# DR.net
KiCad netlist of a schematic drawn in EAGLE
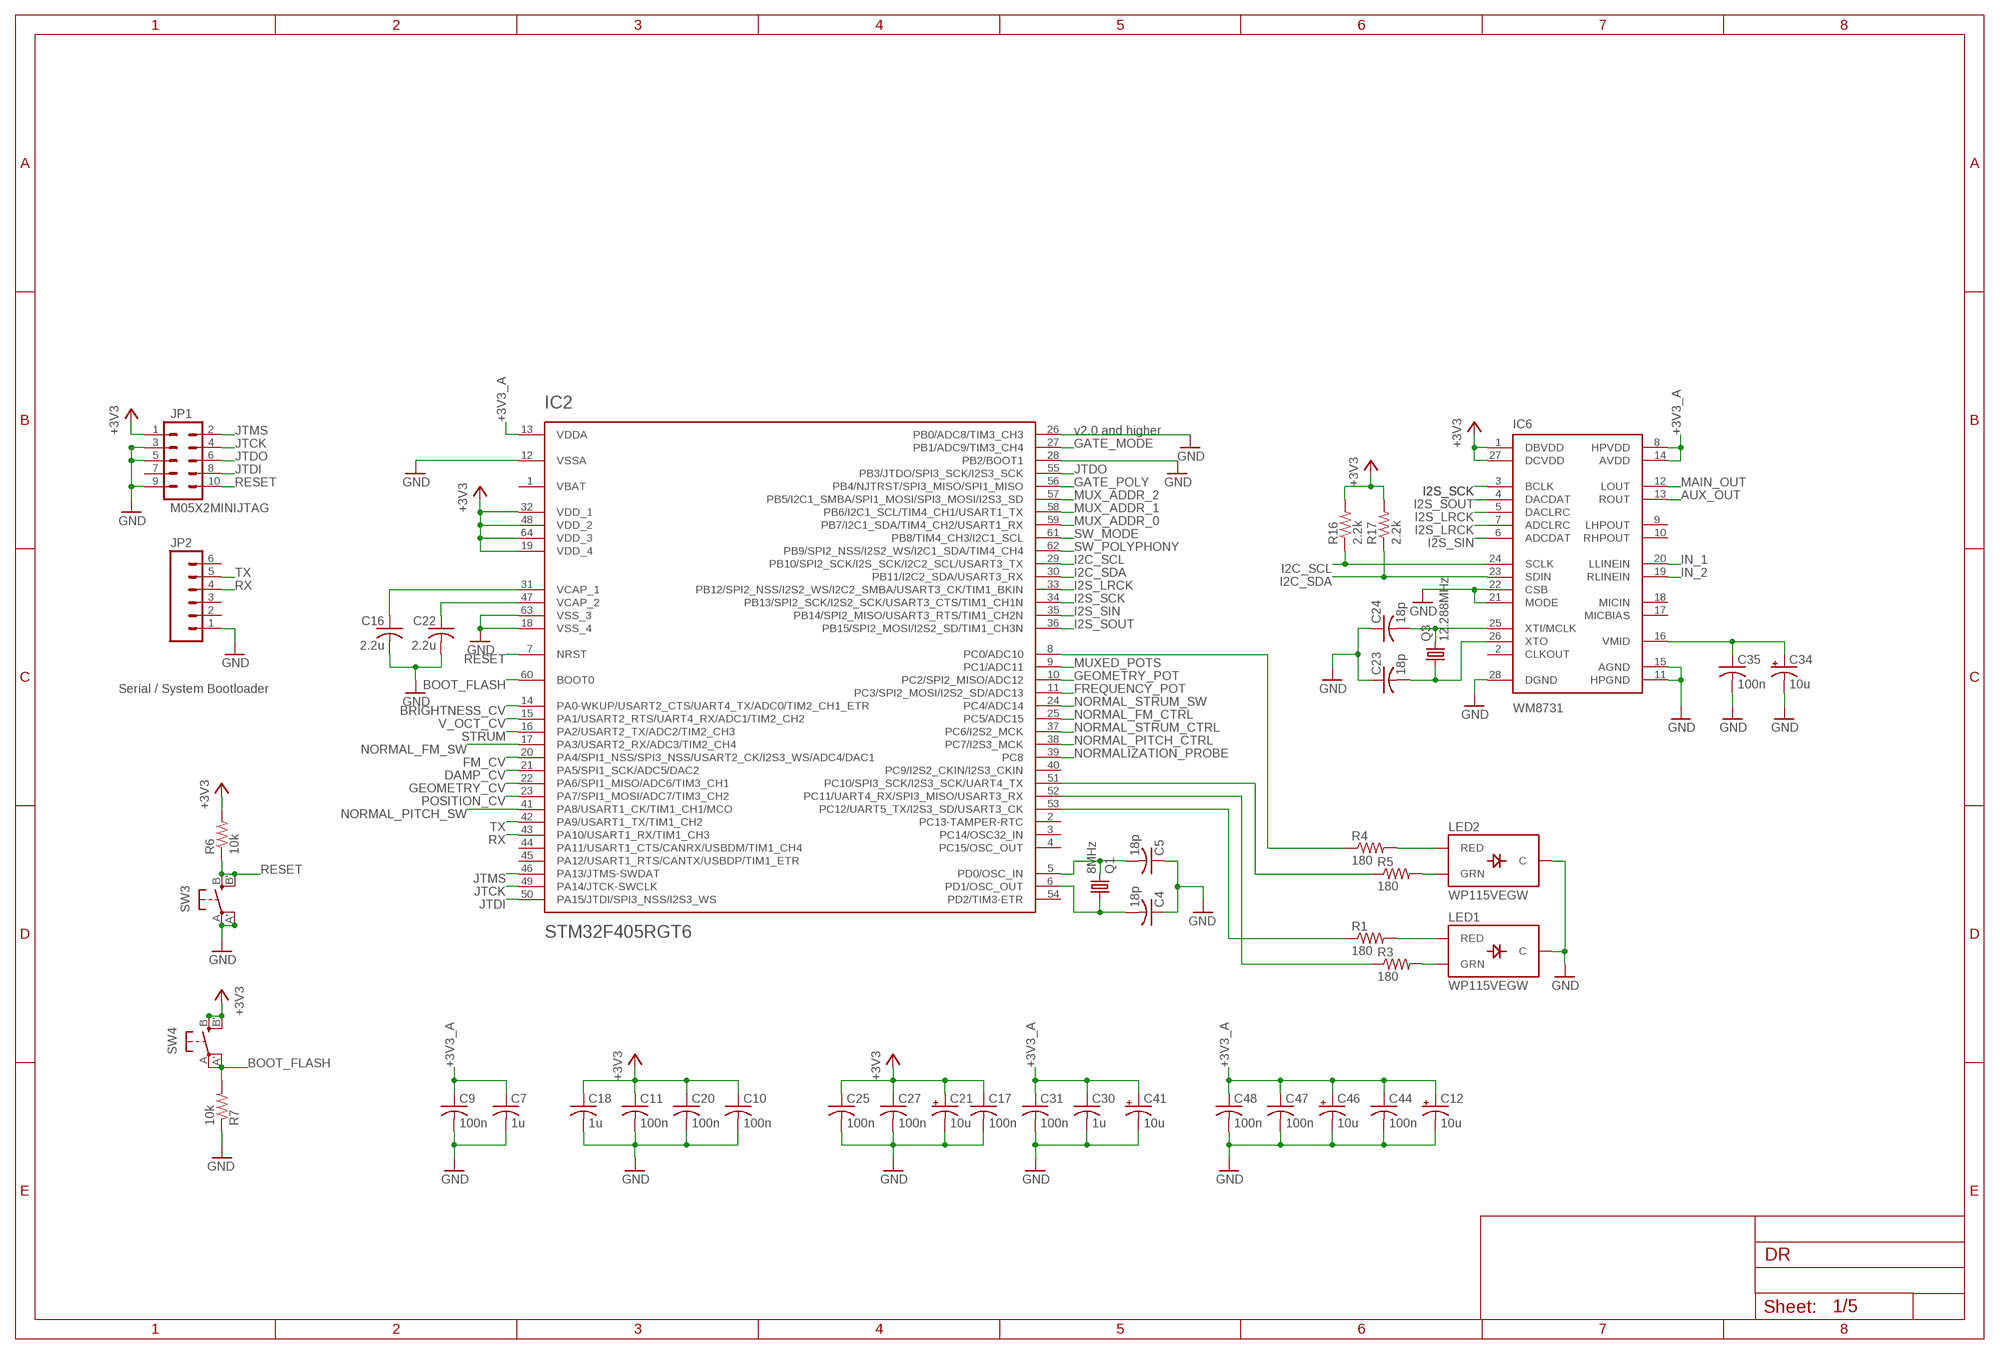
[diagram p0: schematic, sheet 1]
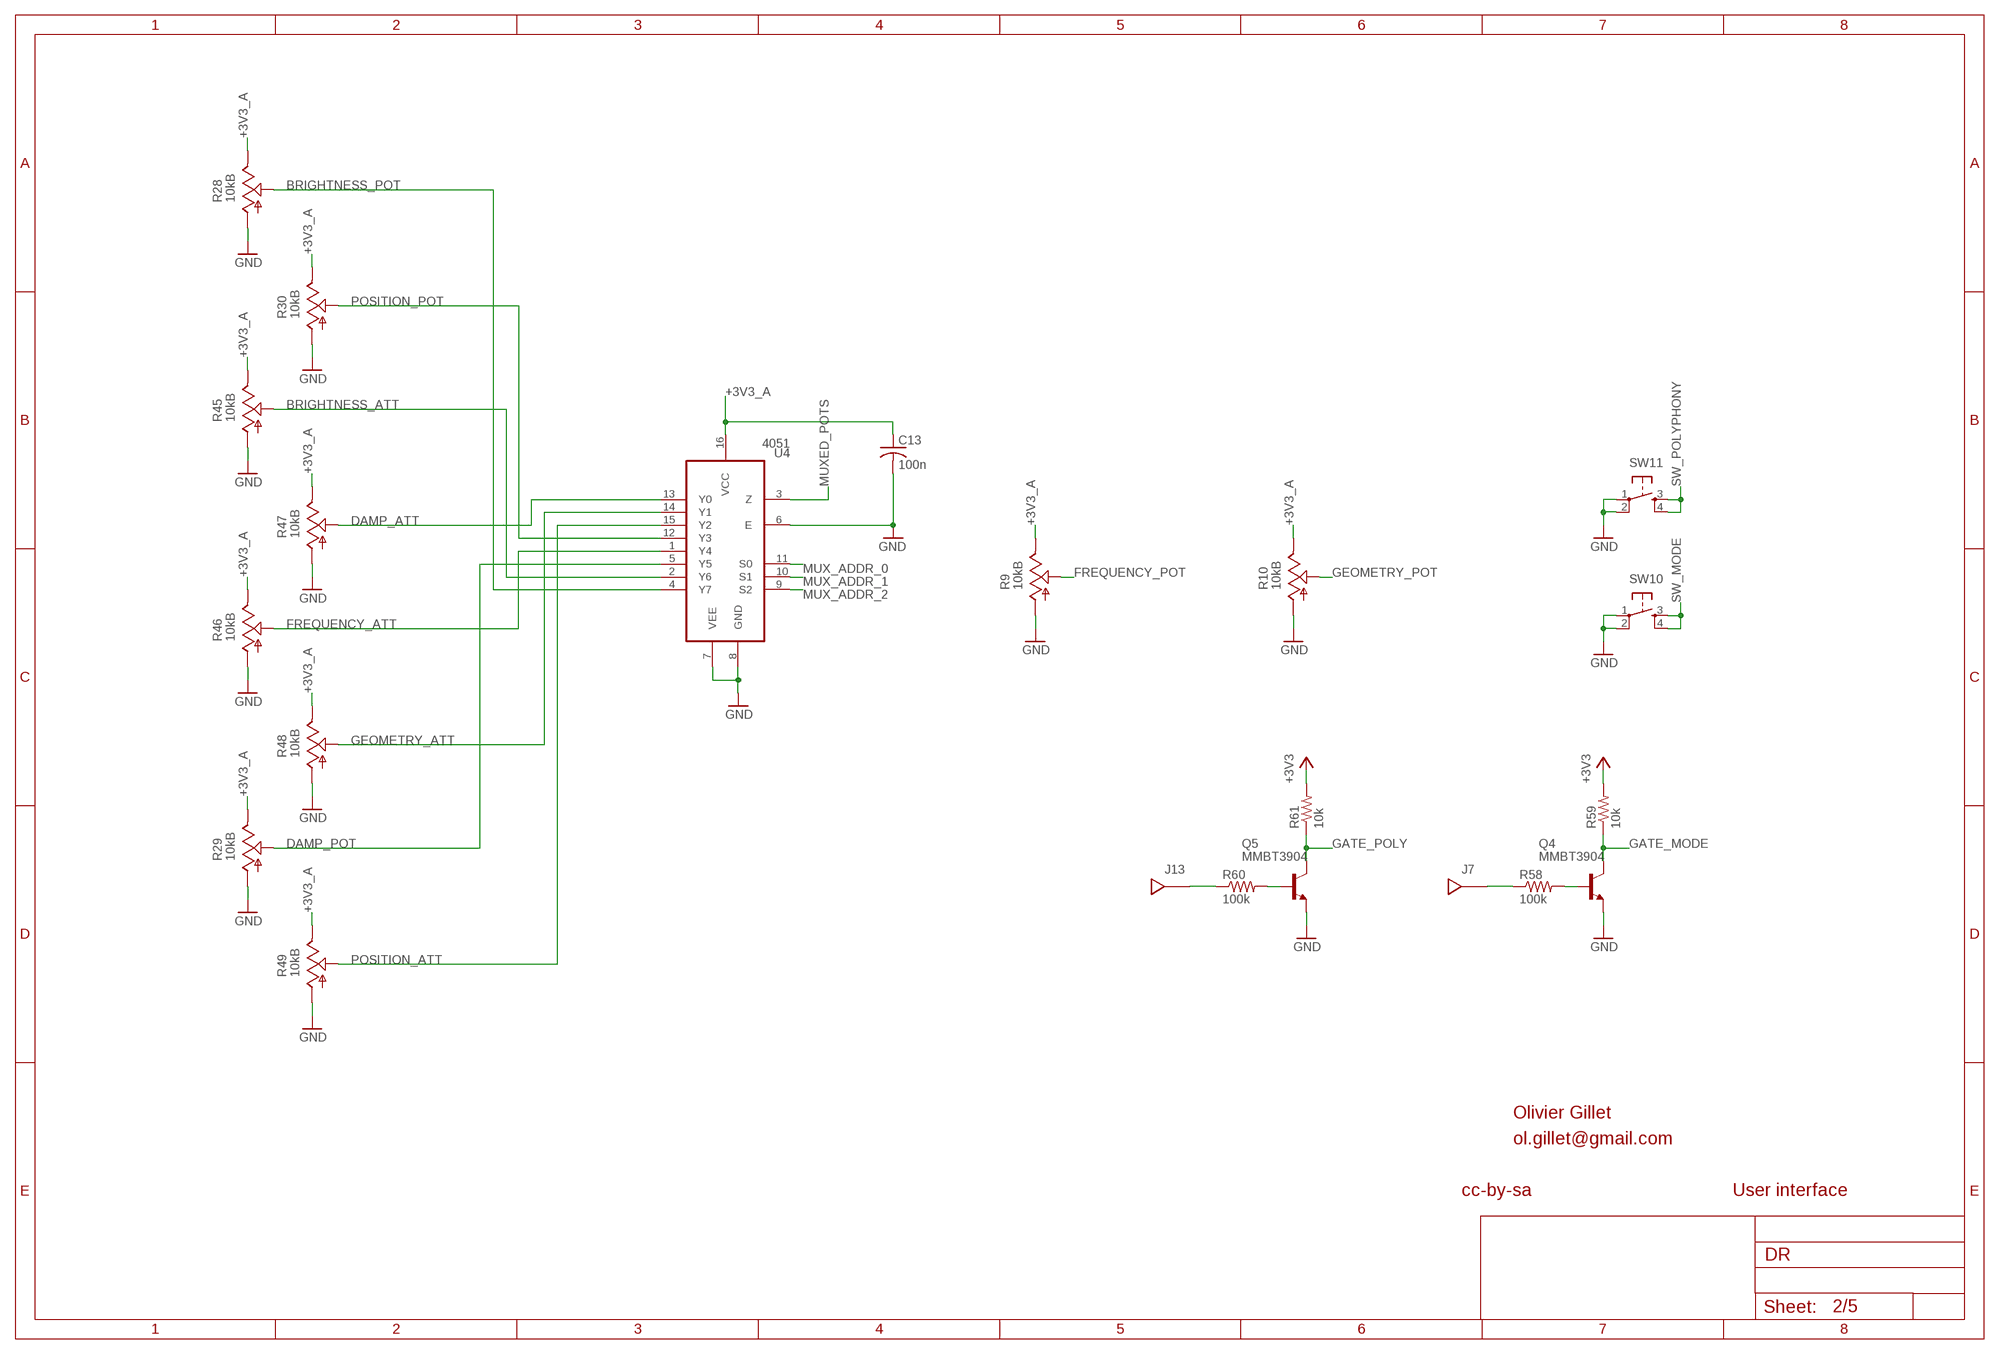
[diagram p1: schematic, sheet 2]
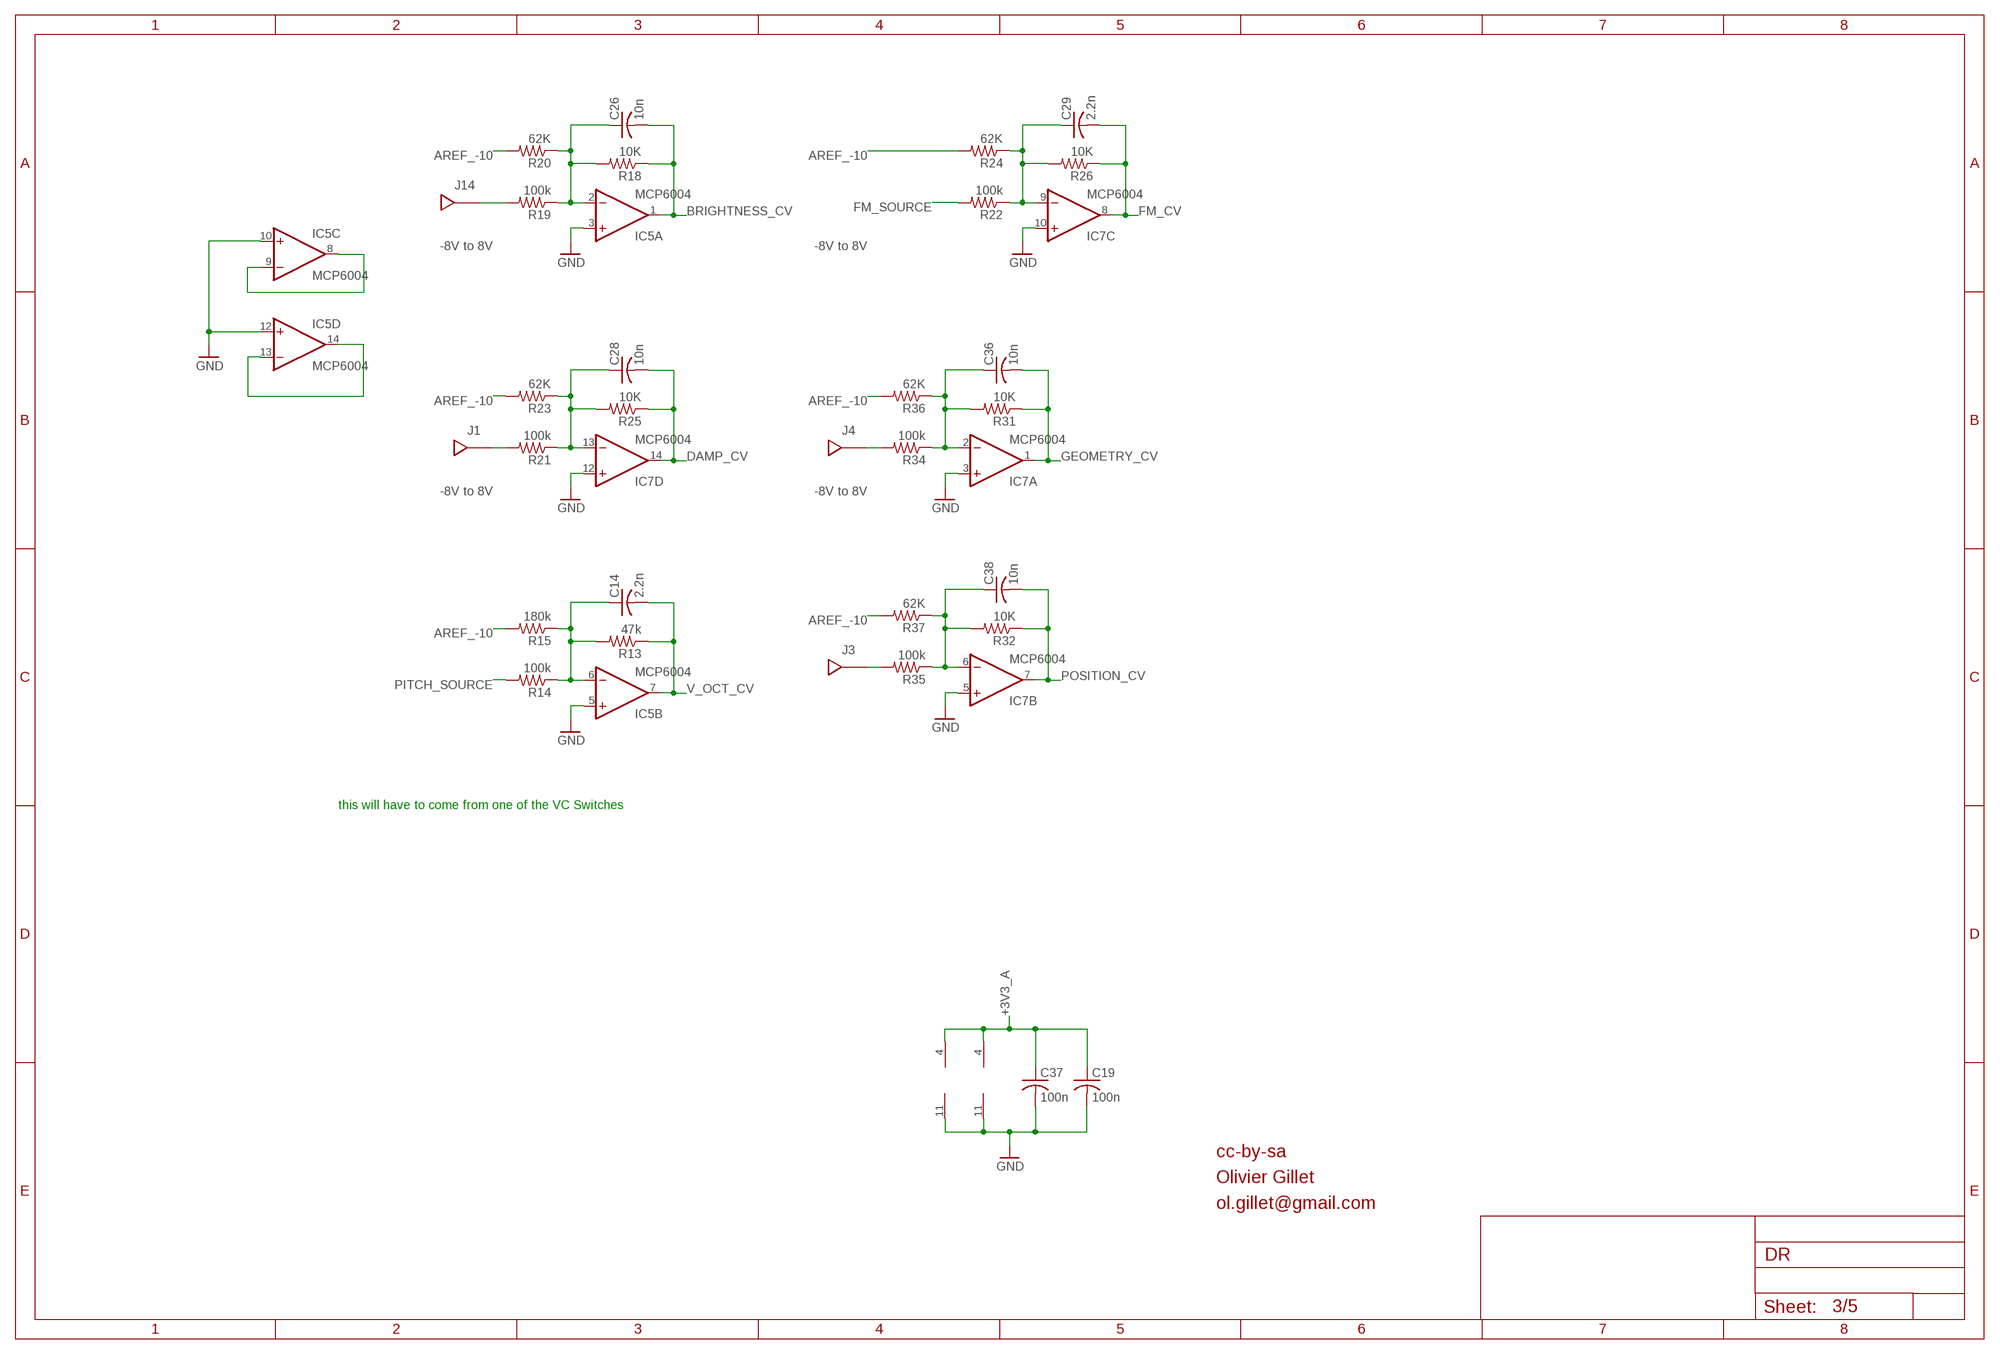
[diagram p2: schematic, sheet 3]
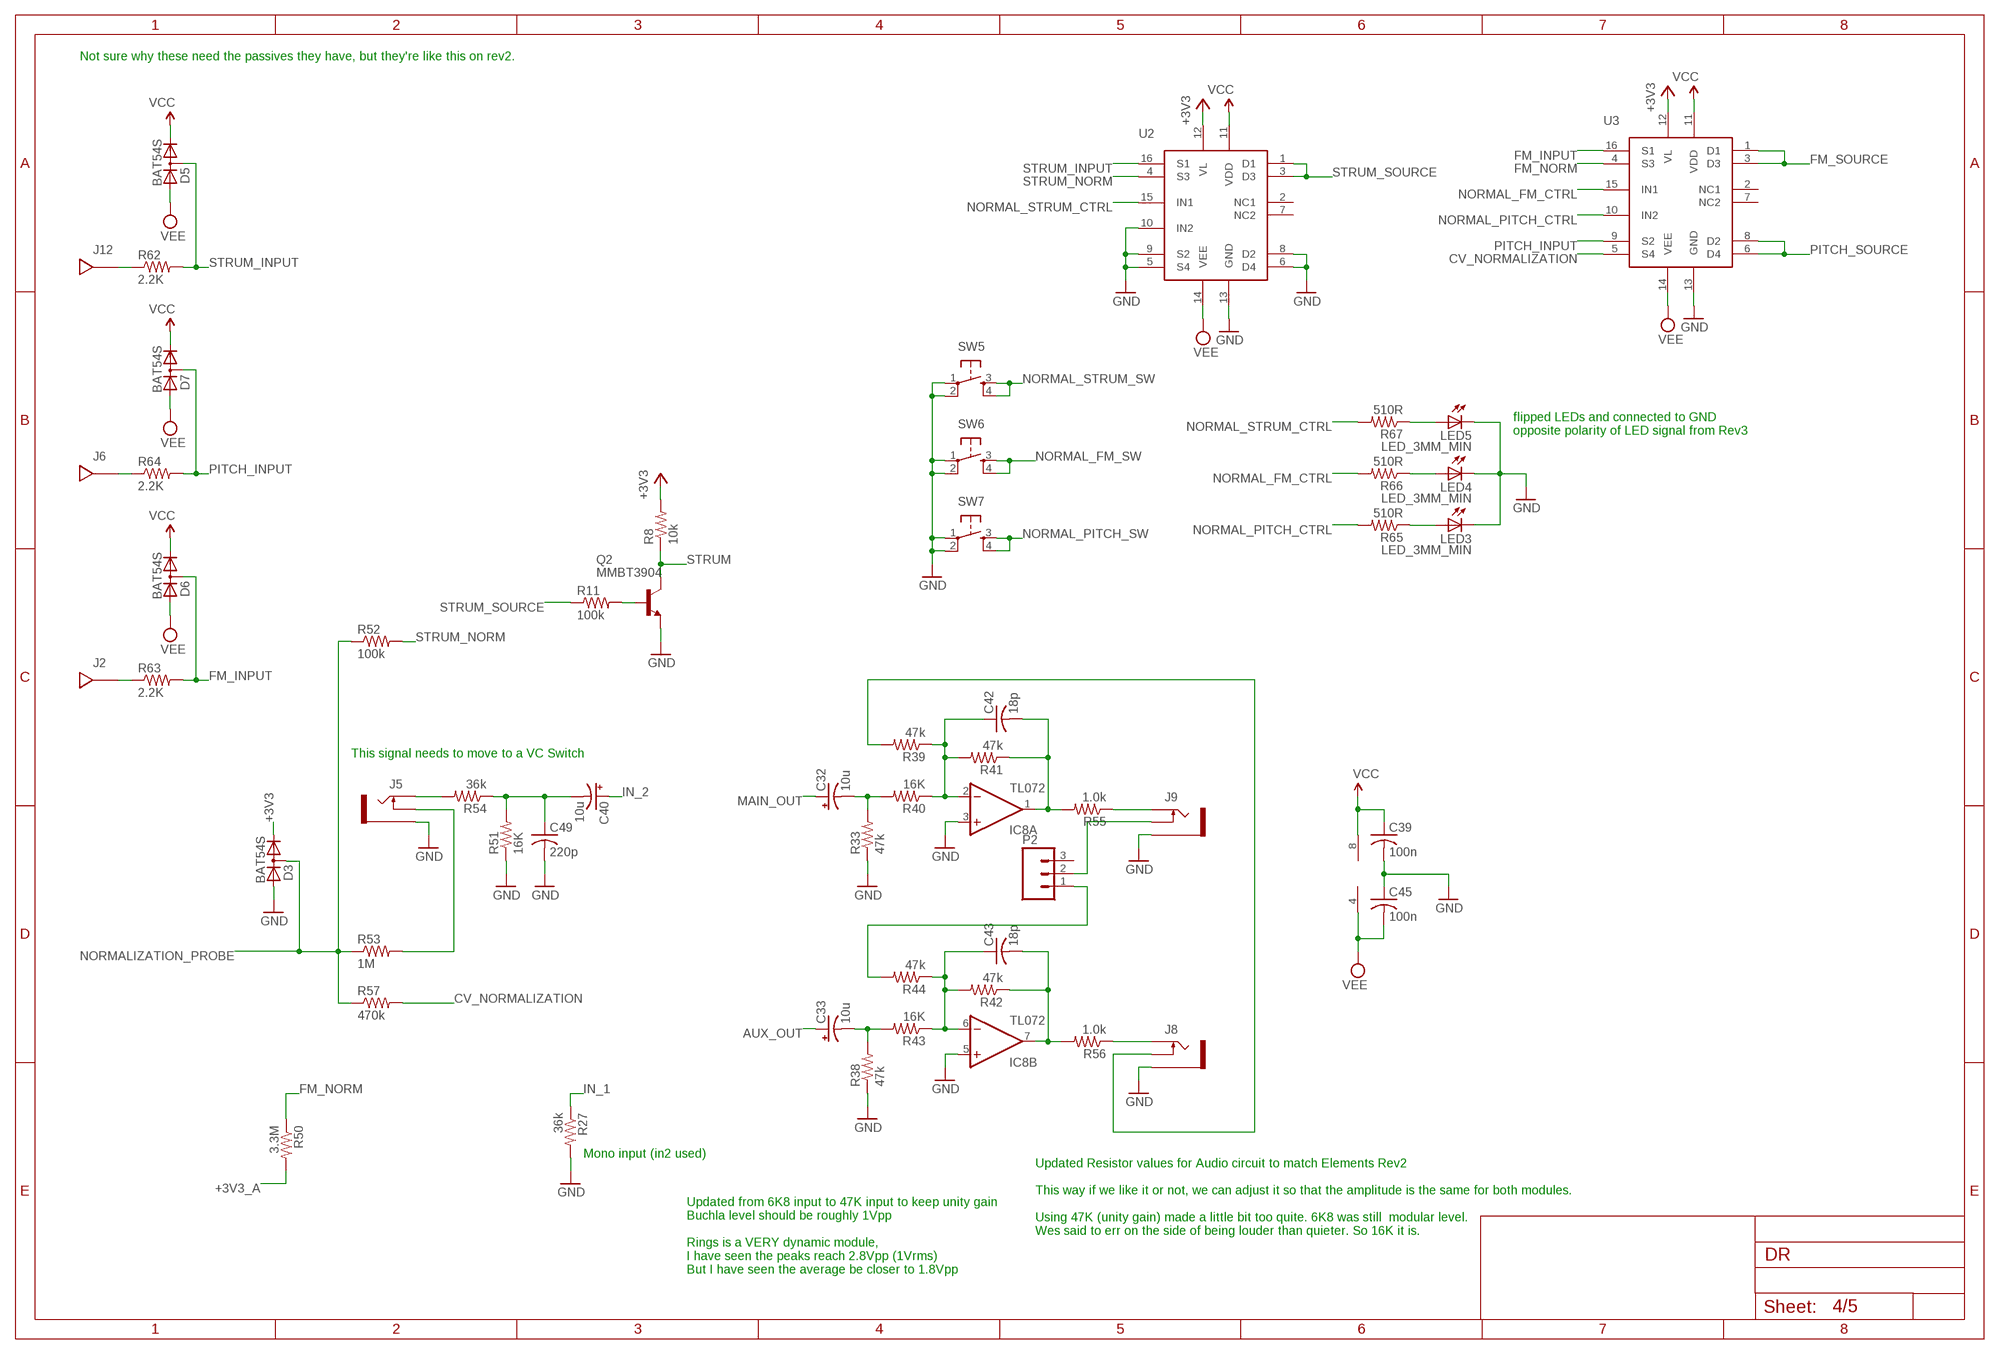
[diagram p3: schematic, sheet 4]
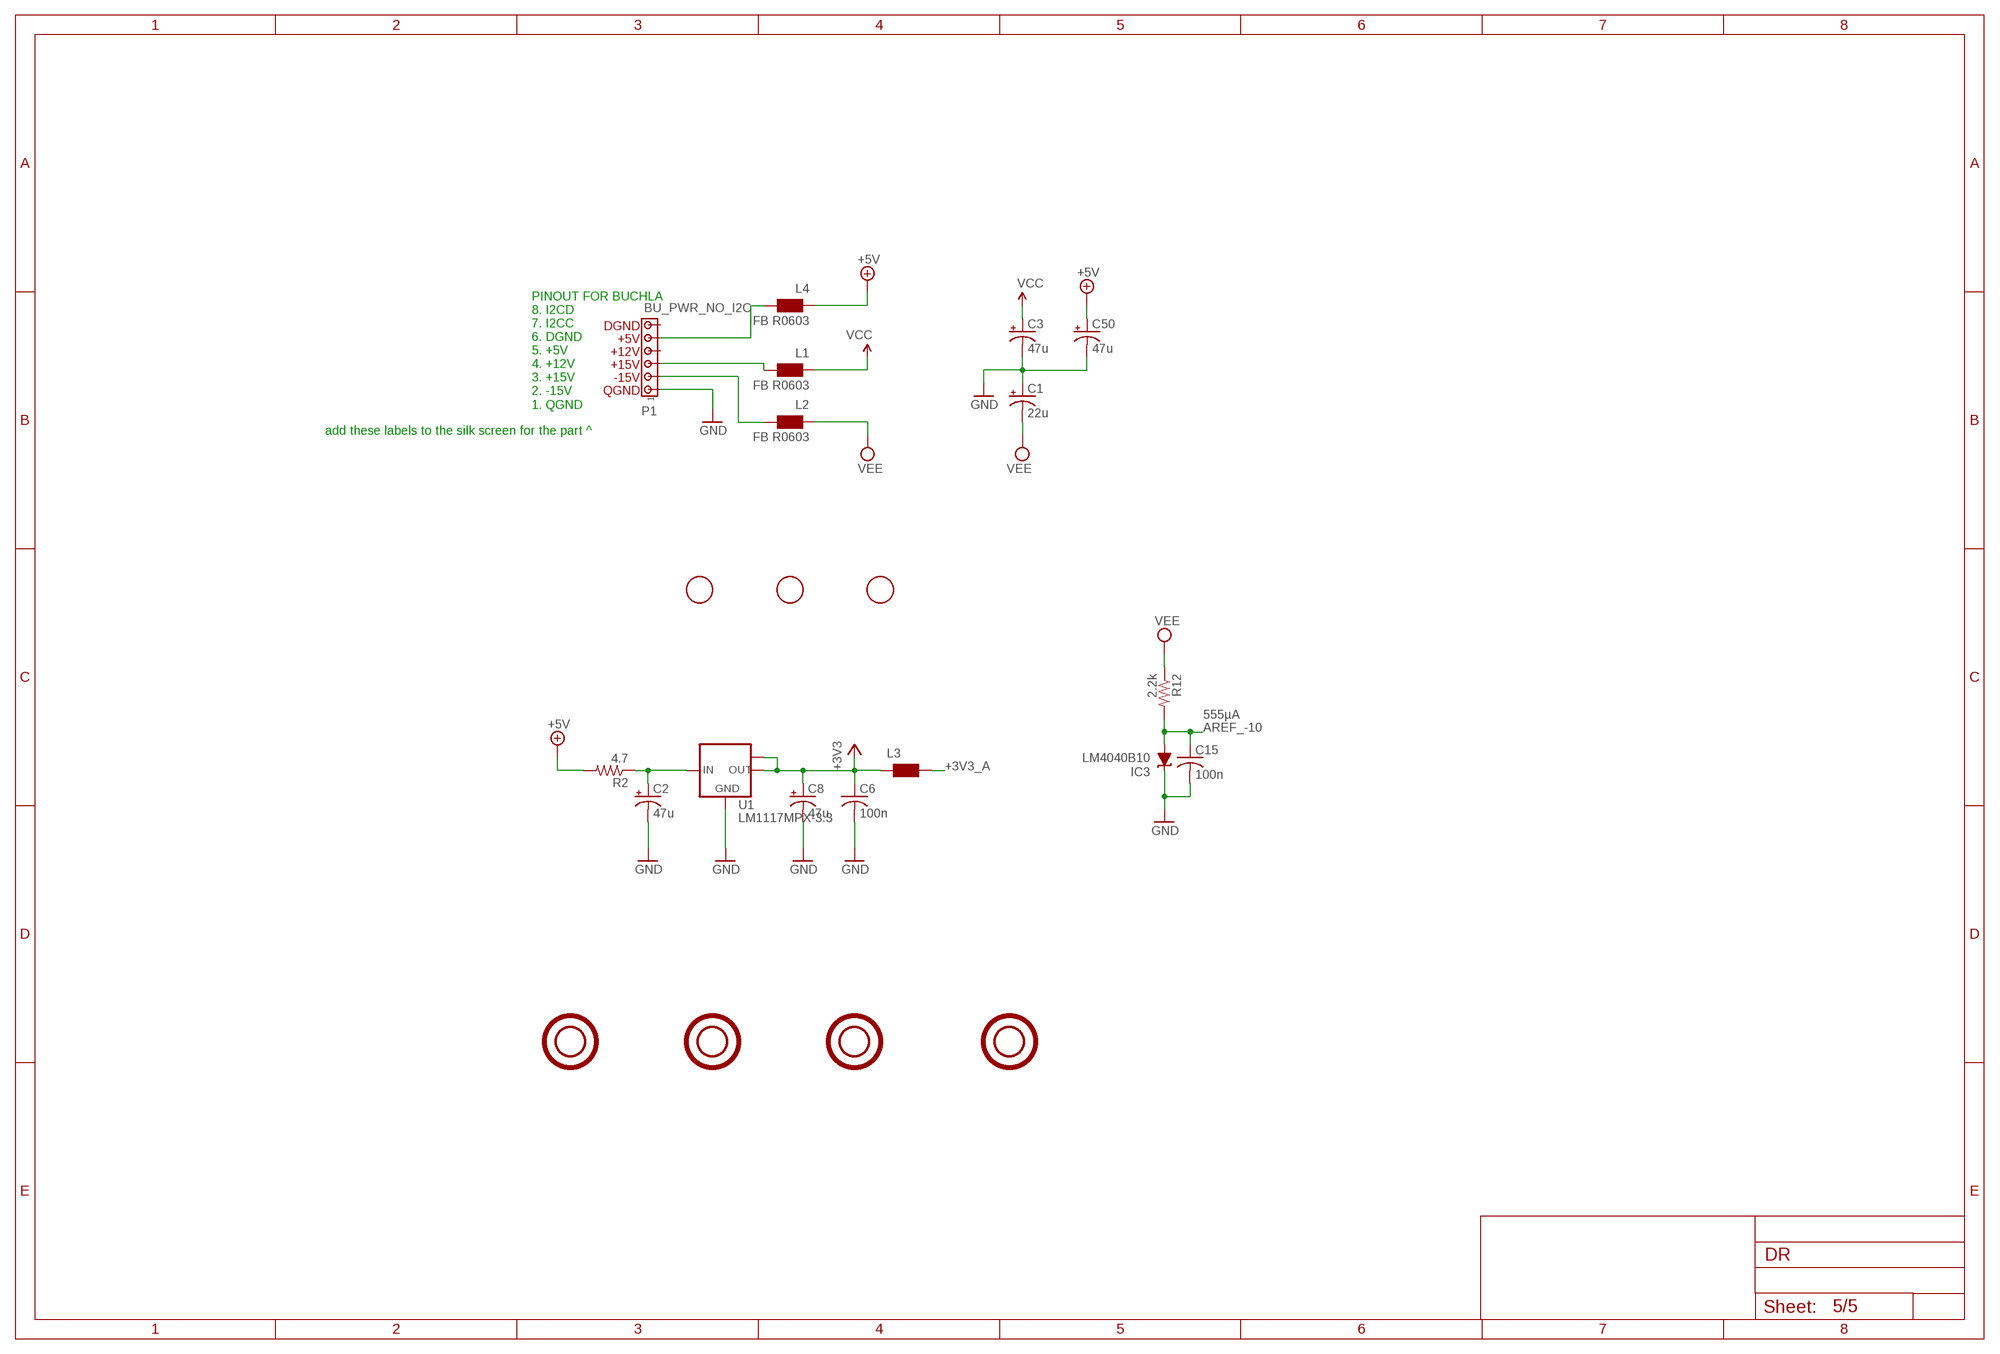
[diagram p4: schematic, sheet 5]

(export (version "E")
  (design (tool "Eeschema 10.0.6"))
  (components
    (comp (ref "C1")
      (value "22u")
      (footprint "eagle-import:PANASONIC_C")
      (libsource (lib "eagle-import") (part "CPOL-USC"))
    )
    (comp (ref "C2")
      (value "47u")
      (footprint "eagle-import:PANASONIC_D")
      (libsource (lib "eagle-import") (part "CPOL-USD"))
    )
    (comp (ref "C3")
      (value "47u")
      (footprint "eagle-import:PANASONIC_D")
      (libsource (lib "eagle-import") (part "CPOL-USD"))
    )
    (comp (ref "C6")
      (value "100n")
      (footprint "eagle-import:C0603")
      (libsource (lib "eagle-import") (part "C-USC0603"))
    )
    (comp (ref "C8")
      (value "47u")
      (footprint "eagle-import:PANASONIC_D")
      (libsource (lib "eagle-import") (part "CPOL-USD"))
    )
    (comp (ref "C15")
      (value "100n")
      (footprint "eagle-import:C0603")
      (libsource (lib "eagle-import") (part "C-USC0603"))
    )
    (comp (ref "C50")
      (value "47u")
      (footprint "eagle-import:PANASONIC_D")
      (libsource (lib "eagle-import") (part "CPOL-USD"))
    )
    (comp (ref "FD1")
      (value "FIDUCIAL")
      (footprint "eagle-import:FIDUCIAL_1MM")
      (libsource (lib "eagle-import") (part "FIDUCIAL"))
    )
    (comp (ref "FD2")
      (value "FIDUCIAL")
      (footprint "eagle-import:FIDUCIAL_1MM")
      (libsource (lib "eagle-import") (part "FIDUCIAL"))
    )
    (comp (ref "FD3")
      (value "FIDUCIAL")
      (footprint "eagle-import:FIDUCIAL_1MM")
      (libsource (lib "eagle-import") (part "FIDUCIAL"))
    )
    (comp (ref "H1")
      (value "3MM_MOUNT_HOLE")
      (footprint "eagle-import:3,0-PAD")
      (libsource (lib "eagle-import") (part "3MM_MOUNT_HOLE"))
    )
    (comp (ref "H2")
      (value "3MM_MOUNT_HOLE")
      (footprint "eagle-import:3,0-PAD")
      (libsource (lib "eagle-import") (part "3MM_MOUNT_HOLE"))
    )
    (comp (ref "H3")
      (value "3MM_MOUNT_HOLE")
      (footprint "eagle-import:3,0-PAD")
      (libsource (lib "eagle-import") (part "3MM_MOUNT_HOLE"))
    )
    (comp (ref "H4")
      (value "3MM_MOUNT_HOLE")
      (footprint "eagle-import:3,0-PAD")
      (libsource (lib "eagle-import") (part "3MM_MOUNT_HOLE"))
    )
    (comp (ref "IC3")
      (value "LM4040B10")
      (footprint "eagle-import:DBZ_R-PDSO-G3")
      (libsource (lib "eagle-import") (part "LM4041DBZB12"))
    )
    (comp (ref "L1")
      (value "FB R0603")
      (footprint "eagle-import:0603")
      (libsource (lib "eagle-import") (part "WE-CBF_0603"))
    )
    (comp (ref "L2")
      (value "FB R0603")
      (footprint "eagle-import:0603")
      (libsource (lib "eagle-import") (part "WE-CBF_0603"))
    )
    (comp (ref "L3")
      (value "WE-CBF_0603")
      (footprint "eagle-import:0603")
      (libsource (lib "eagle-import") (part "WE-CBF_0603"))
    )
    (comp (ref "L4")
      (value "FB R0603")
      (footprint "eagle-import:0603")
      (libsource (lib "eagle-import") (part "WE-CBF_0603"))
    )
    (comp (ref "P1")
      (value "BU_PWR_NO_I2C")
      (footprint "eagle-import:MTA_156")
      (libsource (lib "eagle-import") (part "BU_PWR_NO_I2C"))
    )
    (comp (ref "R2")
      (value "4.7")
      (footprint "eagle-import:R1206")
      (libsource (lib "eagle-import") (part "R-US_R1206"))
    )
    (comp (ref "R12")
      (value "2.2k")
      (footprint "eagle-import:R0603")
      (libsource (lib "eagle-import") (part "R-US_R0603"))
    )
    (comp (ref "U1")
      (value "LM1117MPX-3.3")
      (footprint "eagle-import:SOT223")
      (libsource (lib "eagle-import") (part "LM1117MPX-3.3"))
    )
    (comp (ref "C4")
      (value "18p")
      (footprint "eagle-import:C0603")
      (libsource (lib "eagle-import") (part "C-USC0603"))
    )
    (comp (ref "C5")
      (value "18p")
      (footprint "eagle-import:C0603")
      (libsource (lib "eagle-import") (part "C-USC0603"))
    )
    (comp (ref "C7")
      (value "1u")
      (footprint "eagle-import:C0603")
      (libsource (lib "eagle-import") (part "C-USC0603"))
    )
    (comp (ref "C9")
      (value "100n")
      (footprint "eagle-import:C0603")
      (libsource (lib "eagle-import") (part "C-USC0603"))
    )
    (comp (ref "C10")
      (value "100n")
      (footprint "eagle-import:C0603")
      (libsource (lib "eagle-import") (part "C-USC0603"))
    )
    (comp (ref "C11")
      (value "100n")
      (footprint "eagle-import:C0603")
      (libsource (lib "eagle-import") (part "C-USC0603"))
    )
    (comp (ref "C12")
      (value "10u")
      (footprint "eagle-import:PANASONIC_A")
      (libsource (lib "eagle-import") (part "CPOL-USA"))
    )
    (comp (ref "C16")
      (value "2.2u")
      (footprint "eagle-import:C0805")
      (libsource (lib "eagle-import") (part "C-USC0805"))
    )
    (comp (ref "C17")
      (value "100n")
      (footprint "eagle-import:C0603")
      (libsource (lib "eagle-import") (part "C-USC0603"))
    )
    (comp (ref "C18")
      (value "1u")
      (footprint "eagle-import:C0603")
      (libsource (lib "eagle-import") (part "C-USC0603"))
    )
    (comp (ref "C20")
      (value "100n")
      (footprint "eagle-import:C0603")
      (libsource (lib "eagle-import") (part "C-USC0603"))
    )
    (comp (ref "C21")
      (value "10u")
      (footprint "eagle-import:PANASONIC_A")
      (libsource (lib "eagle-import") (part "CPOL-USA"))
    )
    (comp (ref "C22")
      (value "2.2u")
      (footprint "eagle-import:C0805")
      (libsource (lib "eagle-import") (part "C-USC0805"))
    )
    (comp (ref "C23")
      (value "18p")
      (footprint "eagle-import:C0603")
      (libsource (lib "eagle-import") (part "C-USC0603"))
    )
    (comp (ref "C24")
      (value "18p")
      (footprint "eagle-import:C0603")
      (libsource (lib "eagle-import") (part "C-USC0603"))
    )
    (comp (ref "C25")
      (value "100n")
      (footprint "eagle-import:C0603")
      (libsource (lib "eagle-import") (part "C-USC0603"))
    )
    (comp (ref "C27")
      (value "100n")
      (footprint "eagle-import:C0603")
      (libsource (lib "eagle-import") (part "C-USC0603"))
    )
    (comp (ref "C30")
      (value "1u")
      (footprint "eagle-import:C0603")
      (libsource (lib "eagle-import") (part "C-USC0603"))
    )
    (comp (ref "C31")
      (value "100n")
      (footprint "eagle-import:C0603")
      (libsource (lib "eagle-import") (part "C-USC0603"))
    )
    (comp (ref "C34")
      (value "10u")
      (footprint "eagle-import:PANASONIC_A")
      (libsource (lib "eagle-import") (part "CPOL-USA"))
    )
    (comp (ref "C35")
      (value "100n")
      (footprint "eagle-import:C0603")
      (libsource (lib "eagle-import") (part "C-USC0603"))
    )
    (comp (ref "C41")
      (value "10u")
      (footprint "eagle-import:PANASONIC_A")
      (libsource (lib "eagle-import") (part "CPOL-USA"))
    )
    (comp (ref "C44")
      (value "100n")
      (footprint "eagle-import:C0603")
      (libsource (lib "eagle-import") (part "C-USC0603"))
    )
    (comp (ref "C46")
      (value "10u")
      (footprint "eagle-import:PANASONIC_A")
      (libsource (lib "eagle-import") (part "CPOL-USA"))
    )
    (comp (ref "C47")
      (value "100n")
      (footprint "eagle-import:C0603")
      (libsource (lib "eagle-import") (part "C-USC0603"))
    )
    (comp (ref "C48")
      (value "100n")
      (footprint "eagle-import:C0603")
      (libsource (lib "eagle-import") (part "C-USC0603"))
    )
    (comp (ref "IC2")
      (value "STM32F405RGT6")
      (footprint "eagle-import:TQFP-10X10-64")
      (libsource (lib "eagle-import") (part "STM32F20X"))
    )
    (comp (ref "IC6")
      (value "WM8731")
      (footprint "eagle-import:SSOP28")
      (libsource (lib "eagle-import") (part "WM8731"))
    )
    (comp (ref "JP1")
      (value "M05X2MINIJTAG")
      (footprint "eagle-import:2X5-1.27")
      (libsource (lib "eagle-import") (part "M05X2MINIJTAG"))
    )
    (comp (ref "JP2")
      (value "M06SIP")
      (footprint "eagle-import:1X06")
      (libsource (lib "eagle-import") (part "M06SIP"))
    )
    (comp (ref "LED1")
      (value "WP115VEGW")
      (footprint "eagle-import:LED-BICOLOR-THROUGHHOLE")
      (libsource (lib "eagle-import") (part "LED-BICOLOR-THROUGHHOLE"))
    )
    (comp (ref "LED2")
      (value "WP115VEGW")
      (footprint "eagle-import:LED-BICOLOR-THROUGHHOLE")
      (libsource (lib "eagle-import") (part "LED-BICOLOR-THROUGHHOLE"))
    )
    (comp (ref "Q1")
      (value "8MHz")
      (footprint "eagle-import:HC49UP")
      (libsource (lib "eagle-import") (part "CRYSTALHC49UP"))
    )
    (comp (ref "Q3")
      (value "12.288MHz")
      (footprint "eagle-import:HC49UP")
      (libsource (lib "eagle-import") (part "CRYSTALHC49UP"))
    )
    (comp (ref "R1")
      (value "180")
      (footprint "eagle-import:R0603")
      (libsource (lib "eagle-import") (part "R-US_R0603"))
    )
    (comp (ref "R3")
      (value "180")
      (footprint "eagle-import:R0603")
      (libsource (lib "eagle-import") (part "R-US_R0603"))
    )
    (comp (ref "R4")
      (value "180")
      (footprint "eagle-import:R0603")
      (libsource (lib "eagle-import") (part "R-US_R0603"))
    )
    (comp (ref "R5")
      (value "180")
      (footprint "eagle-import:R0603")
      (libsource (lib "eagle-import") (part "R-US_R0603"))
    )
    (comp (ref "R6")
      (value "10k")
      (footprint "eagle-import:R0603")
      (libsource (lib "eagle-import") (part "R-US_R0603"))
    )
    (comp (ref "R7")
      (value "10k")
      (footprint "eagle-import:R0603")
      (libsource (lib "eagle-import") (part "R-US_R0603"))
    )
    (comp (ref "R16")
      (value "2.2k")
      (footprint "eagle-import:R0603")
      (libsource (lib "eagle-import") (part "R-US_R0603"))
    )
    (comp (ref "R17")
      (value "2.2k")
      (footprint "eagle-import:R0603")
      (libsource (lib "eagle-import") (part "R-US_R0603"))
    )
    (comp (ref "SW3")
      (value "EVQQ2")
      (footprint "eagle-import:EVQ-Q2")
      (libsource (lib "eagle-import") (part "EVQQ2"))
    )
    (comp (ref "SW4")
      (value "EVQQ2")
      (footprint "eagle-import:EVQ-Q2")
      (libsource (lib "eagle-import") (part "EVQQ2"))
    )
    (comp (ref "C14")
      (value "2.2n")
      (footprint "eagle-import:C0603")
      (libsource (lib "eagle-import") (part "C-USC0603"))
    )
    (comp (ref "C19")
      (value "100n")
      (footprint "eagle-import:C0603")
      (libsource (lib "eagle-import") (part "C-USC0603"))
    )
    (comp (ref "C26")
      (value "10n")
      (footprint "eagle-import:C0603")
      (libsource (lib "eagle-import") (part "C-USC0603"))
    )
    (comp (ref "C28")
      (value "10n")
      (footprint "eagle-import:C0603")
      (libsource (lib "eagle-import") (part "C-USC0603"))
    )
    (comp (ref "C29")
      (value "2.2n")
      (footprint "eagle-import:C0603")
      (libsource (lib "eagle-import") (part "C-USC0603"))
    )
    (comp (ref "C36")
      (value "10n")
      (footprint "eagle-import:C0603")
      (libsource (lib "eagle-import") (part "C-USC0603"))
    )
    (comp (ref "C37")
      (value "100n")
      (footprint "eagle-import:C0603")
      (libsource (lib "eagle-import") (part "C-USC0603"))
    )
    (comp (ref "C38")
      (value "10n")
      (footprint "eagle-import:C0603")
      (libsource (lib "eagle-import") (part "C-USC0603"))
    )
    (comp (ref "IC5")
      (value "MCP6004")
      (footprint "eagle-import:SO14")
      (libsource (lib "eagle-import") (part "QUAD_OPAMPD"))
    )
    (comp (ref "IC7")
      (value "MCP6004")
      (footprint "eagle-import:SO14")
      (libsource (lib "eagle-import") (part "QUAD_OPAMPD"))
    )
    (comp (ref "J1")
      (value "JOHNSON_BANANASTD")
      (footprint "eagle-import:JOHNSON")
      (libsource (lib "eagle-import") (part "JOHNSON_BANANASTD"))
    )
    (comp (ref "J3")
      (value "JOHNSON_BANANASTD")
      (footprint "eagle-import:JOHNSON")
      (libsource (lib "eagle-import") (part "JOHNSON_BANANASTD"))
    )
    (comp (ref "J4")
      (value "JOHNSON_BANANASTD")
      (footprint "eagle-import:JOHNSON")
      (libsource (lib "eagle-import") (part "JOHNSON_BANANASTD"))
    )
    (comp (ref "J14")
      (value "JOHNSON_BANANASTD")
      (footprint "eagle-import:JOHNSON")
      (libsource (lib "eagle-import") (part "JOHNSON_BANANASTD"))
    )
    (comp (ref "R13")
      (value "47k")
      (footprint "eagle-import:R0603")
      (libsource (lib "eagle-import") (part "R-US_R0603"))
    )
    (comp (ref "R14")
      (value "100k")
      (footprint "eagle-import:R0603")
      (libsource (lib "eagle-import") (part "R-US_R0603"))
    )
    (comp (ref "R15")
      (value "180k")
      (footprint "eagle-import:R0603")
      (libsource (lib "eagle-import") (part "R-US_R0603"))
    )
    (comp (ref "R18")
      (value "10K")
      (footprint "eagle-import:R0603")
      (libsource (lib "eagle-import") (part "R-US_R0603"))
    )
    (comp (ref "R19")
      (value "100k")
      (footprint "eagle-import:R0603")
      (libsource (lib "eagle-import") (part "R-US_R0603"))
    )
    (comp (ref "R20")
      (value "62K")
      (footprint "eagle-import:R0603")
      (libsource (lib "eagle-import") (part "R-US_R0603"))
    )
    (comp (ref "R21")
      (value "100k")
      (footprint "eagle-import:R0603")
      (libsource (lib "eagle-import") (part "R-US_R0603"))
    )
    (comp (ref "R22")
      (value "100k")
      (footprint "eagle-import:R0603")
      (libsource (lib "eagle-import") (part "R-US_R0603"))
    )
    (comp (ref "R23")
      (value "62K")
      (footprint "eagle-import:R0603")
      (libsource (lib "eagle-import") (part "R-US_R0603"))
    )
    (comp (ref "R24")
      (value "62K")
      (footprint "eagle-import:R0603")
      (libsource (lib "eagle-import") (part "R-US_R0603"))
    )
    (comp (ref "R25")
      (value "10K")
      (footprint "eagle-import:R0603")
      (libsource (lib "eagle-import") (part "R-US_R0603"))
    )
    (comp (ref "R26")
      (value "10K")
      (footprint "eagle-import:R0603")
      (libsource (lib "eagle-import") (part "R-US_R0603"))
    )
    (comp (ref "R31")
      (value "10K")
      (footprint "eagle-import:R0603")
      (libsource (lib "eagle-import") (part "R-US_R0603"))
    )
    (comp (ref "R32")
      (value "10K")
      (footprint "eagle-import:R0603")
      (libsource (lib "eagle-import") (part "R-US_R0603"))
    )
    (comp (ref "R34")
      (value "100k")
      (footprint "eagle-import:R0603")
      (libsource (lib "eagle-import") (part "R-US_R0603"))
    )
    (comp (ref "R35")
      (value "100k")
      (footprint "eagle-import:R0603")
      (libsource (lib "eagle-import") (part "R-US_R0603"))
    )
    (comp (ref "R36")
      (value "62K")
      (footprint "eagle-import:R0603")
      (libsource (lib "eagle-import") (part "R-US_R0603"))
    )
    (comp (ref "R37")
      (value "62K")
      (footprint "eagle-import:R0603")
      (libsource (lib "eagle-import") (part "R-US_R0603"))
    )
    (comp (ref "C13")
      (value "100n")
      (footprint "eagle-import:C0603")
      (libsource (lib "eagle-import") (part "C-USC0603"))
    )
    (comp (ref "J7")
      (value "JOHNSON_BANANASTD")
      (footprint "eagle-import:JOHNSON")
      (libsource (lib "eagle-import") (part "JOHNSON_BANANASTD"))
    )
    (comp (ref "J13")
      (value "JOHNSON_BANANASTD")
      (footprint "eagle-import:JOHNSON")
      (libsource (lib "eagle-import") (part "JOHNSON_BANANASTD"))
    )
    (comp (ref "Q4")
      (value "MMBT3904")
      (footprint "eagle-import:SOT23-BEC")
      (libsource (lib "eagle-import") (part "-NPN-SOT23-BECMMBT3904LT1"))
    )
    (comp (ref "Q5")
      (value "MMBT3904")
      (footprint "eagle-import:SOT23-BEC")
      (libsource (lib "eagle-import") (part "-NPN-SOT23-BECMMBT3904LT1"))
    )
    (comp (ref "R9")
      (value "10kB")
      (footprint "eagle-import:ALPS_POT_VERTICAL_PS")
      (libsource (lib "eagle-import") (part "POT_USVERTICAL_PS"))
    )
    (comp (ref "R10")
      (value "10kB")
      (footprint "eagle-import:ALPS_POT_VERTICAL_PS")
      (libsource (lib "eagle-import") (part "POT_USVERTICAL_PS"))
    )
    (comp (ref "R28")
      (value "10kB")
      (footprint "eagle-import:ALPS_POT_VERTICAL_PS")
      (libsource (lib "eagle-import") (part "POT_USVERTICAL_PS"))
    )
    (comp (ref "R29")
      (value "10kB")
      (footprint "eagle-import:ALPS_POT_VERTICAL_PS")
      (libsource (lib "eagle-import") (part "POT_USVERTICAL_PS"))
    )
    (comp (ref "R30")
      (value "10kB")
      (footprint "eagle-import:ALPS_POT_VERTICAL_PS")
      (libsource (lib "eagle-import") (part "POT_USVERTICAL_PS"))
    )
    (comp (ref "R45")
      (value "10kB")
      (footprint "eagle-import:ALPS_POT_VERTICAL")
      (libsource (lib "eagle-import") (part "POT_USVERTICAL"))
    )
    (comp (ref "R46")
      (value "10kB")
      (footprint "eagle-import:ALPS_POT_VERTICAL")
      (libsource (lib "eagle-import") (part "POT_USVERTICAL"))
    )
    (comp (ref "R47")
      (value "10kB")
      (footprint "eagle-import:ALPS_POT_VERTICAL")
      (libsource (lib "eagle-import") (part "POT_USVERTICAL"))
    )
    (comp (ref "R48")
      (value "10kB")
      (footprint "eagle-import:ALPS_POT_VERTICAL")
      (libsource (lib "eagle-import") (part "POT_USVERTICAL"))
    )
    (comp (ref "R49")
      (value "10kB")
      (footprint "eagle-import:ALPS_POT_VERTICAL")
      (libsource (lib "eagle-import") (part "POT_USVERTICAL"))
    )
    (comp (ref "R58")
      (value "100k")
      (footprint "eagle-import:R0603")
      (libsource (lib "eagle-import") (part "R-US_R0603"))
    )
    (comp (ref "R59")
      (value "10k")
      (footprint "eagle-import:R0603")
      (libsource (lib "eagle-import") (part "R-US_R0603"))
    )
    (comp (ref "R60")
      (value "100k")
      (footprint "eagle-import:R0603")
      (libsource (lib "eagle-import") (part "R-US_R0603"))
    )
    (comp (ref "R61")
      (value "10k")
      (footprint "eagle-import:R0603")
      (libsource (lib "eagle-import") (part "R-US_R0603"))
    )
    (comp (ref "SW10")
      (value "TAC_SWITCH")
      (footprint "eagle-import:C&K_D6R")
      (libsource (lib "eagle-import") (part "TAC_SWITCH"))
    )
    (comp (ref "SW11")
      (value "TAC_SWITCH")
      (footprint "eagle-import:C&K_D6R")
      (libsource (lib "eagle-import") (part "TAC_SWITCH"))
    )
    (comp (ref "U4")
      (value "4051")
      (footprint "eagle-import:SO16")
      (libsource (lib "eagle-import") (part "4051"))
    )
    (comp (ref "C32")
      (value "10u")
      (footprint "eagle-import:PANASONIC_A")
      (libsource (lib "eagle-import") (part "CPOL-USA"))
    )
    (comp (ref "C33")
      (value "10u")
      (footprint "eagle-import:PANASONIC_A")
      (libsource (lib "eagle-import") (part "CPOL-USA"))
    )
    (comp (ref "C39")
      (value "100n")
      (footprint "eagle-import:C0603")
      (libsource (lib "eagle-import") (part "C-USC0603"))
    )
    (comp (ref "C40")
      (value "10u")
      (footprint "eagle-import:PANASONIC_A")
      (libsource (lib "eagle-import") (part "CPOL-USA"))
    )
    (comp (ref "C42")
      (value "18p")
      (footprint "eagle-import:C0603")
      (libsource (lib "eagle-import") (part "C-USC0603"))
    )
    (comp (ref "C43")
      (value "18p")
      (footprint "eagle-import:C0603")
      (libsource (lib "eagle-import") (part "C-USC0603"))
    )
    (comp (ref "C45")
      (value "100n")
      (footprint "eagle-import:C0603")
      (libsource (lib "eagle-import") (part "C-USC0603"))
    )
    (comp (ref "C49")
      (value "220p")
      (footprint "eagle-import:C0603")
      (libsource (lib "eagle-import") (part "C-USC0603"))
    )
    (comp (ref "D3")
      (value "BAT54S")
      (footprint "eagle-import:SOT23")
      (libsource (lib "eagle-import") (part "DIODE_2CACA-SOT23"))
    )
    (comp (ref "D5")
      (value "BAT54S")
      (footprint "eagle-import:SOT23")
      (libsource (lib "eagle-import") (part "DIODE_2CACA-SOT23"))
    )
    (comp (ref "D6")
      (value "BAT54S")
      (footprint "eagle-import:SOT23")
      (libsource (lib "eagle-import") (part "DIODE_2CACA-SOT23"))
    )
    (comp (ref "D7")
      (value "BAT54S")
      (footprint "eagle-import:SOT23")
      (libsource (lib "eagle-import") (part "DIODE_2CACA-SOT23"))
    )
    (comp (ref "IC8")
      (value "TL072")
      (footprint "eagle-import:SO08")
      (libsource (lib "eagle-import") (part "TL072D"))
    )
    (comp (ref "J2")
      (value "JOHNSON_BANANASTD")
      (footprint "eagle-import:JOHNSON")
      (libsource (lib "eagle-import") (part "JOHNSON_BANANASTD"))
    )
    (comp (ref "J5")
      (value "SWITCHCRAFT_42A")
      (footprint "eagle-import:SWITCH_JOHNSON")
      (libsource (lib "eagle-import") (part "SWITCHCRAFT_42A"))
    )
    (comp (ref "J6")
      (value "JOHNSON_BANANASTD")
      (footprint "eagle-import:JOHNSON")
      (libsource (lib "eagle-import") (part "JOHNSON_BANANASTD"))
    )
    (comp (ref "J8")
      (value "SWITCHCRAFT_42A")
      (footprint "eagle-import:SWITCH_JOHNSON")
      (libsource (lib "eagle-import") (part "SWITCHCRAFT_42A"))
    )
    (comp (ref "J9")
      (value "SWITCHCRAFT_42A")
      (footprint "eagle-import:SWITCH_JOHNSON")
      (libsource (lib "eagle-import") (part "SWITCHCRAFT_42A"))
    )
    (comp (ref "J12")
      (value "JOHNSON_BANANASTD")
      (footprint "eagle-import:JOHNSON")
      (libsource (lib "eagle-import") (part "JOHNSON_BANANASTD"))
    )
    (comp (ref "LED3")
      (value "LED_3MM_MIN")
      (footprint "eagle-import:LED_3MM_MIN")
      (libsource (lib "eagle-import") (part "LED_3MM_MIN"))
    )
    (comp (ref "LED4")
      (value "LED_3MM_MIN")
      (footprint "eagle-import:LED_3MM_MIN")
      (libsource (lib "eagle-import") (part "LED_3MM_MIN"))
    )
    (comp (ref "LED5")
      (value "LED_3MM_MIN")
      (footprint "eagle-import:LED_3MM_MIN")
      (libsource (lib "eagle-import") (part "LED_3MM_MIN"))
    )
    (comp (ref "P2")
      (value "M03LOCK")
      (footprint "eagle-import:1X03_LOCK")
      (libsource (lib "eagle-import") (part "M03LOCK"))
    )
    (comp (ref "Q2")
      (value "MMBT3904")
      (footprint "eagle-import:SOT23-BEC")
      (libsource (lib "eagle-import") (part "-NPN-SOT23-BECMMBT3904LT1"))
    )
    (comp (ref "R8")
      (value "10k")
      (footprint "eagle-import:R0603")
      (libsource (lib "eagle-import") (part "R-US_R0603"))
    )
    (comp (ref "R11")
      (value "100k")
      (footprint "eagle-import:R0603")
      (libsource (lib "eagle-import") (part "R-US_R0603"))
    )
    (comp (ref "R27")
      (value "36k")
      (footprint "eagle-import:R0603")
      (libsource (lib "eagle-import") (part "R-US_R0603"))
    )
    (comp (ref "R33")
      (value "47k")
      (footprint "eagle-import:R0603")
      (libsource (lib "eagle-import") (part "R-US_R0603"))
    )
    (comp (ref "R38")
      (value "47k")
      (footprint "eagle-import:R0603")
      (libsource (lib "eagle-import") (part "R-US_R0603"))
    )
    (comp (ref "R39")
      (value "47k")
      (footprint "eagle-import:R0603")
      (libsource (lib "eagle-import") (part "R-US_R0603"))
    )
    (comp (ref "R40")
      (value "16K")
      (footprint "eagle-import:R0603")
      (libsource (lib "eagle-import") (part "R-US_R0603"))
    )
    (comp (ref "R41")
      (value "47k")
      (footprint "eagle-import:R0603")
      (libsource (lib "eagle-import") (part "R-US_R0603"))
    )
    (comp (ref "R42")
      (value "47k")
      (footprint "eagle-import:R0603")
      (libsource (lib "eagle-import") (part "R-US_R0603"))
    )
    (comp (ref "R43")
      (value "16K")
      (footprint "eagle-import:R0603")
      (libsource (lib "eagle-import") (part "R-US_R0603"))
    )
    (comp (ref "R44")
      (value "47k")
      (footprint "eagle-import:R0603")
      (libsource (lib "eagle-import") (part "R-US_R0603"))
    )
    (comp (ref "R50")
      (value "3.3M")
      (footprint "eagle-import:R0603")
      (libsource (lib "eagle-import") (part "R-US_R0603"))
    )
    (comp (ref "R51")
      (value "16K")
      (footprint "eagle-import:R0603")
      (libsource (lib "eagle-import") (part "R-US_R0603"))
    )
    (comp (ref "R52")
      (value "100k")
      (footprint "eagle-import:R0603")
      (libsource (lib "eagle-import") (part "R-US_R0603"))
    )
    (comp (ref "R53")
      (value "1M")
      (footprint "eagle-import:R0603")
      (libsource (lib "eagle-import") (part "R-US_R0603"))
    )
    (comp (ref "R54")
      (value "36k")
      (footprint "eagle-import:R0603")
      (libsource (lib "eagle-import") (part "R-US_R0603"))
    )
    (comp (ref "R55")
      (value "1.0k")
      (footprint "eagle-import:R0603")
      (libsource (lib "eagle-import") (part "R-US_R0603"))
    )
    (comp (ref "R56")
      (value "1.0k")
      (footprint "eagle-import:R0603")
      (libsource (lib "eagle-import") (part "R-US_R0603"))
    )
    (comp (ref "R57")
      (value "470k")
      (footprint "eagle-import:R0603")
      (libsource (lib "eagle-import") (part "R-US_R0603"))
    )
    (comp (ref "R62")
      (value "2.2K")
      (footprint "eagle-import:R0603")
      (libsource (lib "eagle-import") (part "R-US_R0603"))
    )
    (comp (ref "R63")
      (value "2.2K")
      (footprint "eagle-import:R0603")
      (libsource (lib "eagle-import") (part "R-US_R0603"))
    )
    (comp (ref "R64")
      (value "2.2K")
      (footprint "eagle-import:R0603")
      (libsource (lib "eagle-import") (part "R-US_R0603"))
    )
    (comp (ref "R65")
      (value "510R")
      (footprint "eagle-import:R0603")
      (libsource (lib "eagle-import") (part "R-US_R0603"))
    )
    (comp (ref "R66")
      (value "510R")
      (footprint "eagle-import:R0603")
      (libsource (lib "eagle-import") (part "R-US_R0603"))
    )
    (comp (ref "R67")
      (value "510R")
      (footprint "eagle-import:R0603")
      (libsource (lib "eagle-import") (part "R-US_R0603"))
    )
    (comp (ref "SW5")
      (value "TAC_SWITCHPTH")
      (footprint "eagle-import:TACTILE-PTH")
      (libsource (lib "eagle-import") (part "TAC_SWITCHPTH"))
    )
    (comp (ref "SW6")
      (value "TAC_SWITCHPTH")
      (footprint "eagle-import:TACTILE-PTH")
      (libsource (lib "eagle-import") (part "TAC_SWITCHPTH"))
    )
    (comp (ref "SW7")
      (value "TAC_SWITCHPTH")
      (footprint "eagle-import:TACTILE-PTH")
      (libsource (lib "eagle-import") (part "TAC_SWITCHPTH"))
    )
    (comp (ref "U2")
      (value "DG403_ANALOG_SWITCH")
      (footprint "eagle-import:SO16")
      (libsource (lib "eagle-import") (part "DG403_ANALOG_SWITCH"))
    )
    (comp (ref "U3")
      (value "DG403_ANALOG_SWITCH")
      (footprint "eagle-import:SO16")
      (libsource (lib "eagle-import") (part "DG403_ANALOG_SWITCH"))
    )
  )
  (nets
    (net (code "1") (name "+3V3") (class "Default")
      (node (ref "C10") (pin "1") (pinfunction "1_1") (pintype "passive"))
      (node (ref "C11") (pin "1") (pinfunction "1_1") (pintype "passive"))
      (node (ref "C17") (pin "1") (pinfunction "1_1") (pintype "passive"))
      (node (ref "C18") (pin "1") (pinfunction "1_1") (pintype "passive"))
      (node (ref "C20") (pin "1") (pinfunction "1_1") (pintype "passive"))
      (node (ref "C21") (pin "+") (pinfunction "+_+") (pintype "passive"))
      (node (ref "C25") (pin "1") (pinfunction "1_1") (pintype "passive"))
      (node (ref "C27") (pin "1") (pinfunction "1_1") (pintype "passive"))
      (node (ref "C6") (pin "1") (pinfunction "1_1") (pintype "passive"))
      (node (ref "C8") (pin "+") (pinfunction "+_+") (pintype "passive"))
      (node (ref "D3") (pin "2") (pinfunction "C_2") (pintype "passive"))
      (node (ref "IC2") (pin "19") (pinfunction "VDD_4_19") (pintype "power_in"))
      (node (ref "IC2") (pin "32") (pinfunction "VDD_1_32") (pintype "power_in"))
      (node (ref "IC2") (pin "48") (pinfunction "VDD_2_48") (pintype "power_in"))
      (node (ref "IC2") (pin "64") (pinfunction "VDD_3_64") (pintype "power_in"))
      (node (ref "IC6") (pin "1") (pinfunction "DBVDD_1") (pintype "bidirectional"))
      (node (ref "IC6") (pin "27") (pinfunction "DCVDD_27") (pintype "bidirectional"))
      (node (ref "JP1") (pin "1") (pinfunction "1_1") (pintype "passive"))
      (node (ref "L3") (pin "1") (pinfunction "1_1") (pintype "passive"))
      (node (ref "R16") (pin "2") (pinfunction "2_2") (pintype "passive"))
      (node (ref "R17") (pin "2") (pinfunction "2_2") (pintype "passive"))
      (node (ref "R59") (pin "2") (pinfunction "2_2") (pintype "passive"))
      (node (ref "R6") (pin "2") (pinfunction "2_2") (pintype "passive"))
      (node (ref "R61") (pin "2") (pinfunction "2_2") (pintype "passive"))
      (node (ref "R8") (pin "2") (pinfunction "2_2") (pintype "passive"))
      (node (ref "SW4") (pin "B") (pinfunction "S_B") (pintype "passive"))
      (node (ref "SW4") (pin "B'") (pinfunction "S1_B'") (pintype "passive"))
      (node (ref "U1") (pin "2") (pinfunction "OUT_2") (pintype "passive"))
      (node (ref "U1") (pin "TAB") (pinfunction "OUT1_TAB") (pintype "passive"))
      (node (ref "U2") (pin "12") (pinfunction "VL_12") (pintype "bidirectional"))
      (node (ref "U3") (pin "12") (pinfunction "VL_12") (pintype "bidirectional"))
    )
    (net (code "2") (name "+3V3_A") (class "Default")
      (node (ref "C12") (pin "+") (pinfunction "+_+") (pintype "passive"))
      (node (ref "C13") (pin "1") (pinfunction "1_1") (pintype "passive"))
      (node (ref "C19") (pin "1") (pinfunction "1_1") (pintype "passive"))
      (node (ref "C30") (pin "1") (pinfunction "1_1") (pintype "passive"))
      (node (ref "C31") (pin "1") (pinfunction "1_1") (pintype "passive"))
      (node (ref "C37") (pin "1") (pinfunction "1_1") (pintype "passive"))
      (node (ref "C41") (pin "+") (pinfunction "+_+") (pintype "passive"))
      (node (ref "C44") (pin "1") (pinfunction "1_1") (pintype "passive"))
      (node (ref "C46") (pin "+") (pinfunction "+_+") (pintype "passive"))
      (node (ref "C47") (pin "1") (pinfunction "1_1") (pintype "passive"))
      (node (ref "C48") (pin "1") (pinfunction "1_1") (pintype "passive"))
      (node (ref "C7") (pin "1") (pinfunction "1_1") (pintype "passive"))
      (node (ref "C9") (pin "1") (pinfunction "1_1") (pintype "passive"))
      (node (ref "IC2") (pin "13") (pinfunction "VDDA_13") (pintype "power_in"))
      (node (ref "IC5") (pin "4") (pinfunction "V+_4") (pintype "power_in"))
      (node (ref "IC6") (pin "14") (pinfunction "AVDD_14") (pintype "bidirectional"))
      (node (ref "IC6") (pin "8") (pinfunction "HPVDD_8") (pintype "bidirectional"))
      (node (ref "IC7") (pin "4") (pinfunction "V+_4") (pintype "power_in"))
      (node (ref "L3") (pin "2") (pinfunction "2_2") (pintype "passive"))
      (node (ref "R10") (pin "P$1") (pinfunction "E_P$1") (pintype "passive"))
      (node (ref "R28") (pin "P$1") (pinfunction "E_P$1") (pintype "passive"))
      (node (ref "R29") (pin "P$1") (pinfunction "E_P$1") (pintype "passive"))
      (node (ref "R30") (pin "P$1") (pinfunction "E_P$1") (pintype "passive"))
      (node (ref "R45") (pin "P$1") (pinfunction "E_P$1") (pintype "passive"))
      (node (ref "R46") (pin "P$1") (pinfunction "E_P$1") (pintype "passive"))
      (node (ref "R47") (pin "P$1") (pinfunction "E_P$1") (pintype "passive"))
      (node (ref "R48") (pin "P$1") (pinfunction "E_P$1") (pintype "passive"))
      (node (ref "R49") (pin "P$1") (pinfunction "E_P$1") (pintype "passive"))
      (node (ref "R50") (pin "2") (pinfunction "2_2") (pintype "passive"))
      (node (ref "R9") (pin "P$1") (pinfunction "E_P$1") (pintype "passive"))
      (node (ref "U4") (pin "16") (pinfunction "VCC_16") (pintype "power_in"))
    )
    (net (code "3") (name "+5V") (class "Default")
      (node (ref "C50") (pin "+") (pinfunction "+_+") (pintype "passive"))
      (node (ref "L4") (pin "1") (pinfunction "1_1") (pintype "passive"))
      (node (ref "R2") (pin "2") (pinfunction "2_2") (pintype "passive"))
    )
    (net (code "4") (name "AREF_-10") (class "Default")
      (node (ref "C15") (pin "1") (pinfunction "1_1") (pintype "passive"))
      (node (ref "IC3") (pin "2") (pinfunction "A_2") (pintype "passive"))
      (node (ref "R12") (pin "2") (pinfunction "2_2") (pintype "passive"))
      (node (ref "R15") (pin "2") (pinfunction "2_2") (pintype "passive"))
      (node (ref "R20") (pin "2") (pinfunction "2_2") (pintype "passive"))
      (node (ref "R23") (pin "2") (pinfunction "2_2") (pintype "passive"))
      (node (ref "R24") (pin "2") (pinfunction "2_2") (pintype "passive"))
      (node (ref "R36") (pin "2") (pinfunction "2_2") (pintype "passive"))
      (node (ref "R37") (pin "2") (pinfunction "2_2") (pintype "passive"))
    )
    (net (code "5") (name "AUX_OUT") (class "Default")
      (node (ref "C33") (pin "+") (pinfunction "+_+") (pintype "passive"))
      (node (ref "IC6") (pin "13") (pinfunction "ROUT_13") (pintype "bidirectional"))
    )
    (net (code "6") (name "BOOT_FLASH") (class "Default")
      (node (ref "IC2") (pin "60") (pinfunction "BOOT0_60") (pintype "bidirectional"))
      (node (ref "R7") (pin "2") (pinfunction "2_2") (pintype "passive"))
      (node (ref "SW4") (pin "A") (pinfunction "P_A") (pintype "passive"))
      (node (ref "SW4") (pin "A'") (pinfunction "P1_A'") (pintype "passive"))
    )
    (net (code "7") (name "BRIGHTNESS_ATT") (class "Default")
      (node (ref "R45") (pin "P$2") (pinfunction "S_P$2") (pintype "passive"))
      (node (ref "U4") (pin "2") (pinfunction "Y6_2") (pintype "bidirectional"))
    )
    (net (code "8") (name "BRIGHTNESS_CV") (class "Default")
      (node (ref "C26") (pin "2") (pinfunction "2_2") (pintype "passive"))
      (node (ref "IC2") (pin "14") (pinfunction "PA0-WKUP/USART2_CTS/UART4_TX/ADC0/TIM2_CH1_ETR_14") (pintype "bidirectional"))
      (node (ref "IC5") (pin "1") (pinfunction "OUT_1") (pintype "output"))
      (node (ref "R18") (pin "1") (pinfunction "1_1") (pintype "passive"))
    )
    (net (code "9") (name "BRIGHTNESS_POT") (class "Default")
      (node (ref "R28") (pin "P$2") (pinfunction "S_P$2") (pintype "passive"))
      (node (ref "U4") (pin "4") (pinfunction "Y7_4") (pintype "bidirectional"))
    )
    (net (code "10") (name "CV_NORMALIZATION") (class "Default")
      (node (ref "R57") (pin "2") (pinfunction "2_2") (pintype "passive"))
      (node (ref "U3") (pin "5") (pinfunction "S4_5") (pintype "bidirectional"))
    )
    (net (code "11") (name "DAMP_ATT") (class "Default")
      (node (ref "R47") (pin "P$2") (pinfunction "S_P$2") (pintype "passive"))
      (node (ref "U4") (pin "13") (pinfunction "Y0_13") (pintype "bidirectional"))
    )
    (net (code "12") (name "DAMP_CV") (class "Default")
      (node (ref "C28") (pin "2") (pinfunction "2_2") (pintype "passive"))
      (node (ref "IC2") (pin "21") (pinfunction "PA5/SPI1_SCK/ADC5/DAC2_21") (pintype "bidirectional"))
      (node (ref "IC7") (pin "14") (pinfunction "OUT_14") (pintype "output"))
      (node (ref "R25") (pin "1") (pinfunction "1_1") (pintype "passive"))
    )
    (net (code "13") (name "DAMP_POT") (class "Default")
      (node (ref "R29") (pin "P$2") (pinfunction "S_P$2") (pintype "passive"))
      (node (ref "U4") (pin "5") (pinfunction "Y5_5") (pintype "bidirectional"))
    )
    (net (code "14") (name "FM_CV") (class "Default")
      (node (ref "C29") (pin "2") (pinfunction "2_2") (pintype "passive"))
      (node (ref "IC2") (pin "20") (pinfunction "PA4/SPI1_NSS/SPI3_NSS/USART2_CK/I2S3_WS/ADC4/DAC1_20") (pintype "bidirectional"))
      (node (ref "IC7") (pin "8") (pinfunction "OUT_8") (pintype "output"))
      (node (ref "R26") (pin "1") (pinfunction "1_1") (pintype "passive"))
    )
    (net (code "15") (name "FM_INPUT") (class "Default")
      (node (ref "D6") (pin "3") (pinfunction "AC_3") (pintype "passive"))
      (node (ref "R63") (pin "2") (pinfunction "2_2") (pintype "passive"))
      (node (ref "U3") (pin "16") (pinfunction "S1_16") (pintype "bidirectional"))
    )
    (net (code "16") (name "FM_NORM") (class "Default")
      (node (ref "R50") (pin "1") (pinfunction "1_1") (pintype "passive"))
      (node (ref "U3") (pin "4") (pinfunction "S3_4") (pintype "bidirectional"))
    )
    (net (code "17") (name "FM_SOURCE") (class "Default")
      (node (ref "R22") (pin "2") (pinfunction "2_2") (pintype "passive"))
      (node (ref "U3") (pin "1") (pinfunction "D1_1") (pintype "bidirectional"))
      (node (ref "U3") (pin "3") (pinfunction "D3_3") (pintype "bidirectional"))
    )
    (net (code "18") (name "FREQUENCY_ATT") (class "Default")
      (node (ref "R46") (pin "P$2") (pinfunction "S_P$2") (pintype "passive"))
      (node (ref "U4") (pin "1") (pinfunction "Y4_1") (pintype "bidirectional"))
    )
    (net (code "19") (name "FREQUENCY_POT") (class "Default")
      (node (ref "IC2") (pin "11") (pinfunction "PC3/SPI2_MOSI/I2S2_SD/ADC13_11") (pintype "bidirectional"))
      (node (ref "R9") (pin "P$2") (pinfunction "S_P$2") (pintype "passive"))
    )
    (net (code "20") (name "GATE_MODE") (class "Default")
      (node (ref "IC2") (pin "27") (pinfunction "PB1/ADC9/TIM3_CH4_27") (pintype "bidirectional"))
      (node (ref "Q4") (pin "C") (pinfunction "C_C") (pintype "passive"))
      (node (ref "R59") (pin "1") (pinfunction "1_1") (pintype "passive"))
    )
    (net (code "21") (name "GATE_POLY") (class "Default")
      (node (ref "IC2") (pin "56") (pinfunction "PB4/NJTRST/SPI3_MISO/SPI1_MISO_56") (pintype "bidirectional"))
      (node (ref "Q5") (pin "C") (pinfunction "C_C") (pintype "passive"))
      (node (ref "R61") (pin "1") (pinfunction "1_1") (pintype "passive"))
    )
    (net (code "22") (name "GEOMETRY_ATT") (class "Default")
      (node (ref "R48") (pin "P$2") (pinfunction "S_P$2") (pintype "passive"))
      (node (ref "U4") (pin "14") (pinfunction "Y1_14") (pintype "bidirectional"))
    )
    (net (code "23") (name "GEOMETRY_CV") (class "Default")
      (node (ref "C36") (pin "2") (pinfunction "2_2") (pintype "passive"))
      (node (ref "IC2") (pin "22") (pinfunction "PA6/SPI1_MISO/ADC6/TIM3_CH1_22") (pintype "bidirectional"))
      (node (ref "IC7") (pin "1") (pinfunction "OUT_1") (pintype "output"))
      (node (ref "R31") (pin "1") (pinfunction "1_1") (pintype "passive"))
    )
    (net (code "24") (name "GEOMETRY_POT") (class "Default")
      (node (ref "IC2") (pin "10") (pinfunction "PC2/SPI2_MISO/ADC12_10") (pintype "bidirectional"))
      (node (ref "R10") (pin "P$2") (pinfunction "S_P$2") (pintype "passive"))
    )
    (net (code "25") (name "GND") (class "Default")
      (node (ref "C1") (pin "+") (pinfunction "+_+") (pintype "passive"))
      (node (ref "C10") (pin "2") (pinfunction "2_2") (pintype "passive"))
      (node (ref "C11") (pin "2") (pinfunction "2_2") (pintype "passive"))
      (node (ref "C12") (pin "-") (pinfunction "-_-") (pintype "passive"))
      (node (ref "C13") (pin "2") (pinfunction "2_2") (pintype "passive"))
      (node (ref "C15") (pin "2") (pinfunction "2_2") (pintype "passive"))
      (node (ref "C16") (pin "2") (pinfunction "2_2") (pintype "passive"))
      (node (ref "C17") (pin "2") (pinfunction "2_2") (pintype "passive"))
      (node (ref "C18") (pin "2") (pinfunction "2_2") (pintype "passive"))
      (node (ref "C19") (pin "2") (pinfunction "2_2") (pintype "passive"))
      (node (ref "C2") (pin "-") (pinfunction "-_-") (pintype "passive"))
      (node (ref "C20") (pin "2") (pinfunction "2_2") (pintype "passive"))
      (node (ref "C21") (pin "-") (pinfunction "-_-") (pintype "passive"))
      (node (ref "C22") (pin "2") (pinfunction "2_2") (pintype "passive"))
      (node (ref "C23") (pin "1") (pinfunction "1_1") (pintype "passive"))
      (node (ref "C24") (pin "1") (pinfunction "1_1") (pintype "passive"))
      (node (ref "C25") (pin "2") (pinfunction "2_2") (pintype "passive"))
      (node (ref "C27") (pin "2") (pinfunction "2_2") (pintype "passive"))
      (node (ref "C3") (pin "-") (pinfunction "-_-") (pintype "passive"))
      (node (ref "C30") (pin "2") (pinfunction "2_2") (pintype "passive"))
      (node (ref "C31") (pin "2") (pinfunction "2_2") (pintype "passive"))
      (node (ref "C34") (pin "-") (pinfunction "-_-") (pintype "passive"))
      (node (ref "C35") (pin "2") (pinfunction "2_2") (pintype "passive"))
      (node (ref "C37") (pin "2") (pinfunction "2_2") (pintype "passive"))
      (node (ref "C39") (pin "2") (pinfunction "2_2") (pintype "passive"))
      (node (ref "C4") (pin "1") (pinfunction "1_1") (pintype "passive"))
      (node (ref "C41") (pin "-") (pinfunction "-_-") (pintype "passive"))
      (node (ref "C44") (pin "2") (pinfunction "2_2") (pintype "passive"))
      (node (ref "C45") (pin "1") (pinfunction "1_1") (pintype "passive"))
      (node (ref "C46") (pin "-") (pinfunction "-_-") (pintype "passive"))
      (node (ref "C47") (pin "2") (pinfunction "2_2") (pintype "passive"))
      (node (ref "C48") (pin "2") (pinfunction "2_2") (pintype "passive"))
      (node (ref "C49") (pin "2") (pinfunction "2_2") (pintype "passive"))
      (node (ref "C5") (pin "1") (pinfunction "1_1") (pintype "passive"))
      (node (ref "C50") (pin "-") (pinfunction "-_-") (pintype "passive"))
      (node (ref "C6") (pin "2") (pinfunction "2_2") (pintype "passive"))
      (node (ref "C7") (pin "2") (pinfunction "2_2") (pintype "passive"))
      (node (ref "C8") (pin "-") (pinfunction "-_-") (pintype "passive"))
      (node (ref "C9") (pin "2") (pinfunction "2_2") (pintype "passive"))
      (node (ref "D3") (pin "1") (pinfunction "A_1") (pintype "passive"))
      (node (ref "IC2") (pin "12") (pinfunction "VSSA_12") (pintype "power_in"))
      (node (ref "IC2") (pin "18") (pinfunction "VSS_4_18") (pintype "power_in"))
      (node (ref "IC2") (pin "26") (pinfunction "PB0/ADC8/TIM3_CH3_26") (pintype "bidirectional"))
      (node (ref "IC2") (pin "28") (pinfunction "PB2/BOOT1_28") (pintype "bidirectional"))
      (node (ref "IC2") (pin "63") (pinfunction "VSS_3_63") (pintype "power_in"))
      (node (ref "IC3") (pin "1") (pinfunction "C_1") (pintype "passive"))
      (node (ref "IC5") (pin "10") (pinfunction "+IN_10") (pintype "input"))
      (node (ref "IC5") (pin "11") (pinfunction "V-_11") (pintype "power_in"))
      (node (ref "IC5") (pin "12") (pinfunction "+IN_12") (pintype "input"))
      (node (ref "IC5") (pin "3") (pinfunction "+IN_3") (pintype "input"))
      (node (ref "IC5") (pin "5") (pinfunction "+IN_5") (pintype "input"))
      (node (ref "IC6") (pin "11") (pinfunction "HPGND_11") (pintype "bidirectional"))
      (node (ref "IC6") (pin "15") (pinfunction "AGND_15") (pintype "bidirectional"))
      (node (ref "IC6") (pin "21") (pinfunction "MODE_21") (pintype "bidirectional"))
      (node (ref "IC6") (pin "22") (pinfunction "CSB_22") (pintype "bidirectional"))
      (node (ref "IC6") (pin "28") (pinfunction "DGND_28") (pintype "bidirectional"))
      (node (ref "IC7") (pin "10") (pinfunction "+IN_10") (pintype "input"))
      (node (ref "IC7") (pin "11") (pinfunction "V-_11") (pintype "power_in"))
      (node (ref "IC7") (pin "12") (pinfunction "+IN_12") (pintype "input"))
      (node (ref "IC7") (pin "3") (pinfunction "+IN_3") (pintype "input"))
      (node (ref "IC7") (pin "5") (pinfunction "+IN_5") (pintype "input"))
      (node (ref "IC8") (pin "3") (pinfunction "+IN_3") (pintype "input"))
      (node (ref "IC8") (pin "5") (pinfunction "+IN_5") (pintype "input"))
      (node (ref "J5") (pin "G") (pinfunction "1_G") (pintype "passive"))
      (node (ref "J8") (pin "G") (pinfunction "1_G") (pintype "passive"))
      (node (ref "J9") (pin "G") (pinfunction "1_G") (pintype "passive"))
      (node (ref "JP1") (pin "3") (pinfunction "3_3") (pintype "passive"))
      (node (ref "JP1") (pin "5") (pinfunction "5_5") (pintype "passive"))
      (node (ref "JP1") (pin "9") (pinfunction "9_9") (pintype "passive"))
      (node (ref "JP2") (pin "1") (pinfunction "1_1") (pintype "passive"))
      (node (ref "LED1") (pin "2") (pinfunction "C_2") (pintype "bidirectional"))
      (node (ref "LED2") (pin "2") (pinfunction "C_2") (pintype "bidirectional"))
      (node (ref "LED3") (pin "K") (pinfunction "C_K") (pintype "passive"))
      (node (ref "LED4") (pin "K") (pinfunction "C_K") (pintype "passive"))
      (node (ref "LED5") (pin "K") (pinfunction "C_K") (pintype "passive"))
      (node (ref "P1") (pin "1") (pinfunction "1_1") (pintype "passive"))
      (node (ref "Q2") (pin "E") (pinfunction "E_E") (pintype "passive"))
      (node (ref "Q4") (pin "E") (pinfunction "E_E") (pintype "passive"))
      (node (ref "Q5") (pin "E") (pinfunction "E_E") (pintype "passive"))
      (node (ref "R10") (pin "P$3") (pinfunction "A_P$3") (pintype "passive"))
      (node (ref "R27") (pin "2") (pinfunction "2_2") (pintype "passive"))
      (node (ref "R28") (pin "P$3") (pinfunction "A_P$3") (pintype "passive"))
      (node (ref "R29") (pin "P$3") (pinfunction "A_P$3") (pintype "passive"))
      (node (ref "R30") (pin "P$3") (pinfunction "A_P$3") (pintype "passive"))
      (node (ref "R33") (pin "1") (pinfunction "1_1") (pintype "passive"))
      (node (ref "R38") (pin "1") (pinfunction "1_1") (pintype "passive"))
      (node (ref "R45") (pin "P$3") (pinfunction "A_P$3") (pintype "passive"))
      (node (ref "R46") (pin "P$3") (pinfunction "A_P$3") (pintype "passive"))
      (node (ref "R47") (pin "P$3") (pinfunction "A_P$3") (pintype "passive"))
      (node (ref "R48") (pin "P$3") (pinfunction "A_P$3") (pintype "passive"))
      (node (ref "R49") (pin "P$3") (pinfunction "A_P$3") (pintype "passive"))
      (node (ref "R51") (pin "1") (pinfunction "1_1") (pintype "passive"))
      (node (ref "R7") (pin "1") (pinfunction "1_1") (pintype "passive"))
      (node (ref "R9") (pin "P$3") (pinfunction "A_P$3") (pintype "passive"))
      (node (ref "SW10") (pin "1") (pinfunction "1_1") (pintype "passive"))
      (node (ref "SW10") (pin "2") (pinfunction "2_2") (pintype "passive"))
      (node (ref "SW11") (pin "1") (pinfunction "1_1") (pintype "passive"))
      (node (ref "SW11") (pin "2") (pinfunction "2_2") (pintype "passive"))
      (node (ref "SW3") (pin "A") (pinfunction "P_A") (pintype "passive"))
      (node (ref "SW3") (pin "A'") (pinfunction "P1_A'") (pintype "passive"))
      (node (ref "SW5") (pin "1") (pinfunction "1_1") (pintype "passive"))
      (node (ref "SW5") (pin "2") (pinfunction "2_2") (pintype "passive"))
      (node (ref "SW6") (pin "1") (pinfunction "1_1") (pintype "passive"))
      (node (ref "SW6") (pin "2") (pinfunction "2_2") (pintype "passive"))
      (node (ref "SW7") (pin "1") (pinfunction "1_1") (pintype "passive"))
      (node (ref "SW7") (pin "2") (pinfunction "2_2") (pintype "passive"))
      (node (ref "U1") (pin "1") (pinfunction "GND_1") (pintype "input"))
      (node (ref "U2") (pin "10") (pinfunction "IN2_10") (pintype "bidirectional"))
      (node (ref "U2") (pin "13") (pinfunction "GND_13") (pintype "bidirectional"))
      (node (ref "U2") (pin "5") (pinfunction "S4_5") (pintype "bidirectional"))
      (node (ref "U2") (pin "6") (pinfunction "D4_6") (pintype "bidirectional"))
      (node (ref "U2") (pin "8") (pinfunction "D2_8") (pintype "bidirectional"))
      (node (ref "U2") (pin "9") (pinfunction "S2_9") (pintype "bidirectional"))
      (node (ref "U3") (pin "13") (pinfunction "GND_13") (pintype "bidirectional"))
      (node (ref "U4") (pin "6") (pinfunction "E_6") (pintype "bidirectional"))
      (node (ref "U4") (pin "7") (pinfunction "VEE_7") (pintype "power_in"))
      (node (ref "U4") (pin "8") (pinfunction "GND_8") (pintype "power_in"))
    )
    (net (code "26") (name "I2C_SCL") (class "Default")
      (node (ref "IC2") (pin "29") (pinfunction "PB10/SPI2_SCK/I2S_SCK/I2C2_SCL/USART3_TX_29") (pintype "bidirectional"))
      (node (ref "IC6") (pin "24") (pinfunction "SCLK_24") (pintype "bidirectional"))
      (node (ref "R16") (pin "1") (pinfunction "1_1") (pintype "passive"))
    )
    (net (code "27") (name "I2C_SDA") (class "Default")
      (node (ref "IC2") (pin "30") (pinfunction "PB11/I2C2_SDA/USART3_RX_30") (pintype "bidirectional"))
      (node (ref "IC6") (pin "23") (pinfunction "SDIN_23") (pintype "bidirectional"))
      (node (ref "R17") (pin "1") (pinfunction "1_1") (pintype "passive"))
    )
    (net (code "28") (name "I2S_LRCK") (class "Default")
      (node (ref "IC2") (pin "33") (pinfunction "PB12/SPI2_NSS/I2S2_WS/I2C2_SMBA/USART3_CK/TIM1_BKIN_33") (pintype "bidirectional"))
      (node (ref "IC6") (pin "5") (pinfunction "DACLRC_5") (pintype "bidirectional"))
      (node (ref "IC6") (pin "7") (pinfunction "ADCLRC_7") (pintype "bidirectional"))
    )
    (net (code "29") (name "I2S_SCK") (class "Default")
      (node (ref "IC2") (pin "34") (pinfunction "PB13/SPI2_SCK/I2S2_SCK/USART3_CTS/TIM1_CH1N_34") (pintype "bidirectional"))
      (node (ref "IC6") (pin "3") (pinfunction "BCLK_3") (pintype "bidirectional"))
    )
    (net (code "30") (name "I2S_SIN") (class "Default")
      (node (ref "IC2") (pin "35") (pinfunction "PB14/SPI2_MISO/USART3_RTS/TIM1_CH2N_35") (pintype "bidirectional"))
      (node (ref "IC6") (pin "6") (pinfunction "ADCDAT_6") (pintype "bidirectional"))
    )
    (net (code "31") (name "I2S_SOUT") (class "Default")
      (node (ref "IC2") (pin "36") (pinfunction "PB15/SPI2_MOSI/I2S2_SD/TIM1_CH3N_36") (pintype "bidirectional"))
      (node (ref "IC6") (pin "4") (pinfunction "DACDAT_4") (pintype "bidirectional"))
    )
    (net (code "32") (name "IN_1") (class "Default")
      (node (ref "IC6") (pin "20") (pinfunction "LLINEIN_20") (pintype "bidirectional"))
      (node (ref "R27") (pin "1") (pinfunction "1_1") (pintype "passive"))
    )
    (net (code "33") (name "IN_2") (class "Default")
      (node (ref "C40") (pin "+") (pinfunction "+_+") (pintype "passive"))
      (node (ref "IC6") (pin "19") (pinfunction "RLINEIN_19") (pintype "bidirectional"))
    )
    (net (code "34") (name "JTCK") (class "Default")
      (node (ref "IC2") (pin "49") (pinfunction "PA14/JTCK-SWCLK_49") (pintype "bidirectional"))
      (node (ref "JP1") (pin "4") (pinfunction "4_4") (pintype "passive"))
    )
    (net (code "35") (name "JTDI") (class "Default")
      (node (ref "IC2") (pin "50") (pinfunction "PA15/JTDI/SPI3_NSS/I2S3_WS_50") (pintype "bidirectional"))
      (node (ref "JP1") (pin "8") (pinfunction "8_8") (pintype "passive"))
    )
    (net (code "36") (name "JTDO") (class "Default")
      (node (ref "IC2") (pin "55") (pinfunction "PB3/JTDO/SPI3_SCK/I2S3_SCK_55") (pintype "bidirectional"))
      (node (ref "JP1") (pin "6") (pinfunction "6_6") (pintype "passive"))
    )
    (net (code "37") (name "JTMS") (class "Default")
      (node (ref "IC2") (pin "46") (pinfunction "PA13/JTMS-SWDAT_46") (pintype "bidirectional"))
      (node (ref "JP1") (pin "2") (pinfunction "2_2") (pintype "passive"))
    )
    (net (code "38") (name "MAIN_OUT") (class "Default")
      (node (ref "C32") (pin "+") (pinfunction "+_+") (pintype "passive"))
      (node (ref "IC6") (pin "12") (pinfunction "LOUT_12") (pintype "bidirectional"))
    )
    (net (code "39") (name "MUXED_POTS") (class "Default")
      (node (ref "IC2") (pin "9") (pinfunction "PC1/ADC11_9") (pintype "bidirectional"))
      (node (ref "U4") (pin "3") (pinfunction "Z_3") (pintype "bidirectional"))
    )
    (net (code "40") (name "MUX_ADDR_0") (class "Default")
      (node (ref "IC2") (pin "59") (pinfunction "PB7/I2C1_SDA/TIM4_CH2/USART1_RX_59") (pintype "bidirectional"))
      (node (ref "U4") (pin "11") (pinfunction "S0_11") (pintype "input"))
    )
    (net (code "41") (name "MUX_ADDR_1") (class "Default")
      (node (ref "IC2") (pin "58") (pinfunction "PB6/I2C1_SCL/TIM4_CH1/USART1_TX_58") (pintype "bidirectional"))
      (node (ref "U4") (pin "10") (pinfunction "S1_10") (pintype "input"))
    )
    (net (code "42") (name "MUX_ADDR_2") (class "Default")
      (node (ref "IC2") (pin "57") (pinfunction "PB5/I2C1_SMBA/SPI1_MOSI/SPI3_MOSI/I2S3_SD_57") (pintype "bidirectional"))
      (node (ref "U4") (pin "9") (pinfunction "S2_9") (pintype "input"))
    )
    (net (code "43") (name "NORMALIZATION_PROBE") (class "Default")
      (node (ref "D3") (pin "3") (pinfunction "AC_3") (pintype "passive"))
      (node (ref "IC2") (pin "39") (pinfunction "PC8_39") (pintype "bidirectional"))
      (node (ref "R52") (pin "1") (pinfunction "1_1") (pintype "passive"))
      (node (ref "R53") (pin "1") (pinfunction "1_1") (pintype "passive"))
      (node (ref "R57") (pin "1") (pinfunction "1_1") (pintype "passive"))
    )
    (net (code "44") (name "NORMAL_FM_CTRL") (class "Default")
      (node (ref "IC2") (pin "25") (pinfunction "PC5/ADC15_25") (pintype "bidirectional"))
      (node (ref "R66") (pin "2") (pinfunction "2_2") (pintype "passive"))
      (node (ref "U3") (pin "15") (pinfunction "IN1_15") (pintype "bidirectional"))
    )
    (net (code "45") (name "NORMAL_FM_SW") (class "Default")
      (node (ref "IC2") (pin "17") (pinfunction "PA3/USART2_RX/ADC3/TIM2_CH4_17") (pintype "bidirectional"))
      (node (ref "SW6") (pin "3") (pinfunction "3_3") (pintype "passive"))
      (node (ref "SW6") (pin "4") (pinfunction "4_4") (pintype "passive"))
    )
    (net (code "46") (name "NORMAL_PITCH_CTRL") (class "Default")
      (node (ref "IC2") (pin "38") (pinfunction "PC7/I2S3_MCK_38") (pintype "bidirectional"))
      (node (ref "R65") (pin "2") (pinfunction "2_2") (pintype "passive"))
      (node (ref "U3") (pin "10") (pinfunction "IN2_10") (pintype "bidirectional"))
    )
    (net (code "47") (name "NORMAL_PITCH_SW") (class "Default")
      (node (ref "IC2") (pin "41") (pinfunction "PA8/USART1_CK/TIM1_CH1/MCO_41") (pintype "bidirectional"))
      (node (ref "SW7") (pin "3") (pinfunction "3_3") (pintype "passive"))
      (node (ref "SW7") (pin "4") (pinfunction "4_4") (pintype "passive"))
    )
    (net (code "48") (name "NORMAL_STRUM_CTRL") (class "Default")
      (node (ref "IC2") (pin "37") (pinfunction "PC6/I2S2_MCK_37") (pintype "bidirectional"))
      (node (ref "R67") (pin "2") (pinfunction "2_2") (pintype "passive"))
      (node (ref "U2") (pin "15") (pinfunction "IN1_15") (pintype "bidirectional"))
    )
    (net (code "49") (name "NORMAL_STRUM_SW") (class "Default")
      (node (ref "IC2") (pin "24") (pinfunction "PC4/ADC14_24") (pintype "bidirectional"))
      (node (ref "SW5") (pin "3") (pinfunction "3_3") (pintype "passive"))
      (node (ref "SW5") (pin "4") (pinfunction "4_4") (pintype "passive"))
    )
    (net (code "50") (name "Net-(C32-Pad-)") (class "Default")
      (node (ref "C32") (pin "-") (pinfunction "-_-") (pintype "passive"))
      (node (ref "R33") (pin "2") (pinfunction "2_2") (pintype "passive"))
      (node (ref "R40") (pin "2") (pinfunction "2_2") (pintype "passive"))
    )
    (net (code "51") (name "Net-(C33-Pad-)") (class "Default")
      (node (ref "C33") (pin "-") (pinfunction "-_-") (pintype "passive"))
      (node (ref "R38") (pin "2") (pinfunction "2_2") (pintype "passive"))
      (node (ref "R43") (pin "2") (pinfunction "2_2") (pintype "passive"))
    )
    (net (code "52") (name "Net-(C40-Pad-)") (class "Default")
      (node (ref "C40") (pin "-") (pinfunction "-_-") (pintype "passive"))
      (node (ref "C49") (pin "1") (pinfunction "1_1") (pintype "passive"))
      (node (ref "R51") (pin "2") (pinfunction "2_2") (pintype "passive"))
      (node (ref "R54") (pin "1") (pinfunction "1_1") (pintype "passive"))
    )
    (net (code "53") (name "Net-(IC2-PC0{slash}ADC10)") (class "Default")
      (node (ref "IC2") (pin "8") (pinfunction "PC0/ADC10_8") (pintype "bidirectional"))
      (node (ref "R4") (pin "1") (pinfunction "1_1") (pintype "passive"))
    )
    (net (code "54") (name "Net-(IC2-PC10{slash}SPI3_SCK{slash}I2S3_SCK{slash}UART4_TX)") (class "Default")
      (node (ref "IC2") (pin "51") (pinfunction "PC10/SPI3_SCK/I2S3_SCK/UART4_TX_51") (pintype "bidirectional"))
      (node (ref "R5") (pin "1") (pinfunction "1_1") (pintype "passive"))
    )
    (net (code "55") (name "Net-(IC2-PC11{slash}UART4_RX{slash}SPI3_MISO{slash}USART3_RX)") (class "Default")
      (node (ref "IC2") (pin "52") (pinfunction "PC11/UART4_RX/SPI3_MISO/USART3_RX_52") (pintype "bidirectional"))
      (node (ref "R3") (pin "1") (pinfunction "1_1") (pintype "passive"))
    )
    (net (code "56") (name "Net-(IC2-PC12{slash}UART5_TX{slash}I2S3_SD{slash}USART3_CK)") (class "Default")
      (node (ref "IC2") (pin "53") (pinfunction "PC12/UART5_TX/I2S3_SD/USART3_CK_53") (pintype "bidirectional"))
      (node (ref "R1") (pin "1") (pinfunction "1_1") (pintype "passive"))
    )
    (net (code "57") (name "Net-(IC2-PD0{slash}OSC_IN)") (class "Default")
      (node (ref "C5") (pin "2") (pinfunction "2_2") (pintype "passive"))
      (node (ref "IC2") (pin "5") (pinfunction "PD0/OSC_IN_5") (pintype "bidirectional"))
      (node (ref "Q1") (pin "2") (pinfunction "2_2") (pintype "passive"))
    )
    (net (code "58") (name "Net-(IC2-PD1{slash}OSC_OUT)") (class "Default")
      (node (ref "C4") (pin "2") (pinfunction "2_2") (pintype "passive"))
      (node (ref "IC2") (pin "6") (pinfunction "PD1/OSC_OUT_6") (pintype "bidirectional"))
      (node (ref "Q1") (pin "1") (pinfunction "1_1") (pintype "passive"))
    )
    (net (code "59") (name "Net-(IC2-VCAP_1)") (class "Default")
      (node (ref "C16") (pin "1") (pinfunction "1_1") (pintype "passive"))
      (node (ref "IC2") (pin "31") (pinfunction "VCAP_1_31") (pintype "power_in"))
    )
    (net (code "60") (name "Net-(IC2-VCAP_2)") (class "Default")
      (node (ref "C22") (pin "1") (pinfunction "1_1") (pintype "passive"))
      (node (ref "IC2") (pin "47") (pinfunction "VCAP_2_47") (pintype "power_in"))
    )
    (net (code "61") (name "Net-(IC5A--IN)") (class "Default")
      (node (ref "C26") (pin "1") (pinfunction "1_1") (pintype "passive"))
      (node (ref "IC5") (pin "2") (pinfunction "-IN_2") (pintype "input"))
      (node (ref "R18") (pin "2") (pinfunction "2_2") (pintype "passive"))
      (node (ref "R19") (pin "1") (pinfunction "1_1") (pintype "passive"))
      (node (ref "R20") (pin "1") (pinfunction "1_1") (pintype "passive"))
    )
    (net (code "62") (name "Net-(IC5B--IN)") (class "Default")
      (node (ref "C14") (pin "1") (pinfunction "1_1") (pintype "passive"))
      (node (ref "IC5") (pin "6") (pinfunction "-IN_6") (pintype "input"))
      (node (ref "R13") (pin "2") (pinfunction "2_2") (pintype "passive"))
      (node (ref "R14") (pin "1") (pinfunction "1_1") (pintype "passive"))
      (node (ref "R15") (pin "1") (pinfunction "1_1") (pintype "passive"))
    )
    (net (code "63") (name "Net-(IC5C--IN)") (class "Default")
      (node (ref "IC5") (pin "8") (pinfunction "OUT_8") (pintype "output"))
      (node (ref "IC5") (pin "9") (pinfunction "-IN_9") (pintype "input"))
    )
    (net (code "64") (name "Net-(IC5D--IN)") (class "Default")
      (node (ref "IC5") (pin "13") (pinfunction "-IN_13") (pintype "input"))
      (node (ref "IC5") (pin "14") (pinfunction "OUT_14") (pintype "output"))
    )
    (net (code "65") (name "Net-(IC6-VMID)") (class "Default")
      (node (ref "C34") (pin "+") (pinfunction "+_+") (pintype "passive"))
      (node (ref "C35") (pin "1") (pinfunction "1_1") (pintype "passive"))
      (node (ref "IC6") (pin "16") (pinfunction "VMID_16") (pintype "bidirectional"))
    )
    (net (code "66") (name "Net-(IC6-XTI{slash}MCLK)") (class "Default")
      (node (ref "C24") (pin "2") (pinfunction "2_2") (pintype "passive"))
      (node (ref "IC6") (pin "25") (pinfunction "XTI/MCLK_25") (pintype "bidirectional"))
      (node (ref "Q3") (pin "2") (pinfunction "2_2") (pintype "passive"))
    )
    (net (code "67") (name "Net-(IC6-XTO)") (class "Default")
      (node (ref "C23") (pin "2") (pinfunction "2_2") (pintype "passive"))
      (node (ref "IC6") (pin "26") (pinfunction "XTO_26") (pintype "bidirectional"))
      (node (ref "Q3") (pin "1") (pinfunction "1_1") (pintype "passive"))
    )
    (net (code "68") (name "Net-(IC7A--IN)") (class "Default")
      (node (ref "C36") (pin "1") (pinfunction "1_1") (pintype "passive"))
      (node (ref "IC7") (pin "2") (pinfunction "-IN_2") (pintype "input"))
      (node (ref "R31") (pin "2") (pinfunction "2_2") (pintype "passive"))
      (node (ref "R34") (pin "1") (pinfunction "1_1") (pintype "passive"))
      (node (ref "R36") (pin "1") (pinfunction "1_1") (pintype "passive"))
    )
    (net (code "69") (name "Net-(IC7B--IN)") (class "Default")
      (node (ref "C38") (pin "1") (pinfunction "1_1") (pintype "passive"))
      (node (ref "IC7") (pin "6") (pinfunction "-IN_6") (pintype "input"))
      (node (ref "R32") (pin "2") (pinfunction "2_2") (pintype "passive"))
      (node (ref "R35") (pin "1") (pinfunction "1_1") (pintype "passive"))
      (node (ref "R37") (pin "1") (pinfunction "1_1") (pintype "passive"))
    )
    (net (code "70") (name "Net-(IC7C--IN)") (class "Default")
      (node (ref "C29") (pin "1") (pinfunction "1_1") (pintype "passive"))
      (node (ref "IC7") (pin "9") (pinfunction "-IN_9") (pintype "input"))
      (node (ref "R22") (pin "1") (pinfunction "1_1") (pintype "passive"))
      (node (ref "R24") (pin "1") (pinfunction "1_1") (pintype "passive"))
      (node (ref "R26") (pin "2") (pinfunction "2_2") (pintype "passive"))
    )
    (net (code "71") (name "Net-(IC7D--IN)") (class "Default")
      (node (ref "C28") (pin "1") (pinfunction "1_1") (pintype "passive"))
      (node (ref "IC7") (pin "13") (pinfunction "-IN_13") (pintype "input"))
      (node (ref "R21") (pin "1") (pinfunction "1_1") (pintype "passive"))
      (node (ref "R23") (pin "1") (pinfunction "1_1") (pintype "passive"))
      (node (ref "R25") (pin "2") (pinfunction "2_2") (pintype "passive"))
    )
    (net (code "72") (name "Net-(IC8A--IN)") (class "Default")
      (node (ref "C42") (pin "1") (pinfunction "1_1") (pintype "passive"))
      (node (ref "IC8") (pin "2") (pinfunction "-IN_2") (pintype "input"))
      (node (ref "R39") (pin "1") (pinfunction "1_1") (pintype "passive"))
      (node (ref "R40") (pin "1") (pinfunction "1_1") (pintype "passive"))
      (node (ref "R41") (pin "2") (pinfunction "2_2") (pintype "passive"))
    )
    (net (code "73") (name "Net-(IC8A-OUT)") (class "Default")
      (node (ref "C42") (pin "2") (pinfunction "2_2") (pintype "passive"))
      (node (ref "IC8") (pin "1") (pinfunction "OUT_1") (pintype "output"))
      (node (ref "R41") (pin "1") (pinfunction "1_1") (pintype "passive"))
      (node (ref "R55") (pin "2") (pinfunction "2_2") (pintype "passive"))
    )
    (net (code "74") (name "Net-(IC8B--IN)") (class "Default")
      (node (ref "C43") (pin "1") (pinfunction "1_1") (pintype "passive"))
      (node (ref "IC8") (pin "6") (pinfunction "-IN_6") (pintype "input"))
      (node (ref "R42") (pin "2") (pinfunction "2_2") (pintype "passive"))
      (node (ref "R43") (pin "1") (pinfunction "1_1") (pintype "passive"))
      (node (ref "R44") (pin "1") (pinfunction "1_1") (pintype "passive"))
    )
    (net (code "75") (name "Net-(IC8B-OUT)") (class "Default")
      (node (ref "C43") (pin "2") (pinfunction "2_2") (pintype "passive"))
      (node (ref "IC8") (pin "7") (pinfunction "OUT_7") (pintype "output"))
      (node (ref "R42") (pin "1") (pinfunction "1_1") (pintype "passive"))
      (node (ref "R56") (pin "2") (pinfunction "2_2") (pintype "passive"))
    )
    (net (code "76") (name "Net-(J1-Pad1)") (class "Default")
      (node (ref "J1") (pin "1") (pinfunction "1_1") (pintype "output"))
      (node (ref "R21") (pin "2") (pinfunction "2_2") (pintype "passive"))
    )
    (net (code "77") (name "Net-(J2-Pad1)") (class "Default")
      (node (ref "J2") (pin "1") (pinfunction "1_1") (pintype "output"))
      (node (ref "R63") (pin "1") (pinfunction "1_1") (pintype "passive"))
    )
    (net (code "78") (name "Net-(J3-Pad1)") (class "Default")
      (node (ref "J3") (pin "1") (pinfunction "1_1") (pintype "output"))
      (node (ref "R35") (pin "2") (pinfunction "2_2") (pintype "passive"))
    )
    (net (code "79") (name "Net-(J4-Pad1)") (class "Default")
      (node (ref "J4") (pin "1") (pinfunction "1_1") (pintype "output"))
      (node (ref "R34") (pin "2") (pinfunction "2_2") (pintype "passive"))
    )
    (net (code "80") (name "Net-(J5-2)") (class "Default")
      (node (ref "J5") (pin "C") (pinfunction "2_C") (pintype "passive"))
      (node (ref "R53") (pin "2") (pinfunction "2_2") (pintype "passive"))
    )
    (net (code "81") (name "Net-(J5-3)") (class "Default")
      (node (ref "J5") (pin "S") (pinfunction "3_S") (pintype "passive"))
      (node (ref "R54") (pin "2") (pinfunction "2_2") (pintype "passive"))
    )
    (net (code "82") (name "Net-(J6-Pad1)") (class "Default")
      (node (ref "J6") (pin "1") (pinfunction "1_1") (pintype "output"))
      (node (ref "R64") (pin "1") (pinfunction "1_1") (pintype "passive"))
    )
    (net (code "83") (name "Net-(J7-Pad1)") (class "Default")
      (node (ref "J7") (pin "1") (pinfunction "1_1") (pintype "output"))
      (node (ref "R58") (pin "1") (pinfunction "1_1") (pintype "passive"))
    )
    (net (code "84") (name "Net-(J8-2)") (class "Default")
      (node (ref "J8") (pin "C") (pinfunction "2_C") (pintype "passive"))
      (node (ref "R39") (pin "2") (pinfunction "2_2") (pintype "passive"))
    )
    (net (code "85") (name "Net-(J8-3)") (class "Default")
      (node (ref "J8") (pin "S") (pinfunction "3_S") (pintype "passive"))
      (node (ref "R56") (pin "1") (pinfunction "1_1") (pintype "passive"))
    )
    (net (code "86") (name "Net-(J9-2)") (class "Default")
      (node (ref "J9") (pin "C") (pinfunction "2_C") (pintype "passive"))
      (node (ref "P2") (pin "2") (pinfunction "2_2") (pintype "passive"))
    )
    (net (code "87") (name "Net-(J9-3)") (class "Default")
      (node (ref "J9") (pin "S") (pinfunction "3_S") (pintype "passive"))
      (node (ref "R55") (pin "1") (pinfunction "1_1") (pintype "passive"))
    )
    (net (code "88") (name "Net-(J12-Pad1)") (class "Default")
      (node (ref "J12") (pin "1") (pinfunction "1_1") (pintype "output"))
      (node (ref "R62") (pin "1") (pinfunction "1_1") (pintype "passive"))
    )
    (net (code "89") (name "Net-(J13-Pad1)") (class "Default")
      (node (ref "J13") (pin "1") (pinfunction "1_1") (pintype "output"))
      (node (ref "R60") (pin "1") (pinfunction "1_1") (pintype "passive"))
    )
    (net (code "90") (name "Net-(J14-Pad1)") (class "Default")
      (node (ref "J14") (pin "1") (pinfunction "1_1") (pintype "output"))
      (node (ref "R19") (pin "2") (pinfunction "2_2") (pintype "passive"))
    )
    (net (code "91") (name "Net-(L1-Pad2)") (class "Default")
      (node (ref "L1") (pin "2") (pinfunction "2_2") (pintype "passive"))
      (node (ref "P1") (pin "3") (pinfunction "3_3") (pintype "passive"))
    )
    (net (code "92") (name "Net-(L2-Pad2)") (class "Default")
      (node (ref "L2") (pin "2") (pinfunction "2_2") (pintype "passive"))
      (node (ref "P1") (pin "2") (pinfunction "2_2") (pintype "passive"))
    )
    (net (code "93") (name "Net-(L4-Pad2)") (class "Default")
      (node (ref "L4") (pin "2") (pinfunction "2_2") (pintype "passive"))
      (node (ref "P1") (pin "5") (pinfunction "5_5") (pintype "passive"))
    )
    (net (code "94") (name "Net-(LED1-GRN)") (class "Default")
      (node (ref "LED1") (pin "1") (pinfunction "GRN_1") (pintype "bidirectional"))
      (node (ref "R3") (pin "2") (pinfunction "2_2") (pintype "passive"))
    )
    (net (code "95") (name "Net-(LED1-RED)") (class "Default")
      (node (ref "LED1") (pin "3") (pinfunction "RED_3") (pintype "bidirectional"))
      (node (ref "R1") (pin "2") (pinfunction "2_2") (pintype "passive"))
    )
    (net (code "96") (name "Net-(LED2-GRN)") (class "Default")
      (node (ref "LED2") (pin "1") (pinfunction "GRN_1") (pintype "bidirectional"))
      (node (ref "R5") (pin "2") (pinfunction "2_2") (pintype "passive"))
    )
    (net (code "97") (name "Net-(LED2-RED)") (class "Default")
      (node (ref "LED2") (pin "3") (pinfunction "RED_3") (pintype "bidirectional"))
      (node (ref "R4") (pin "2") (pinfunction "2_2") (pintype "passive"))
    )
    (net (code "98") (name "Net-(LED3-PadA)") (class "Default")
      (node (ref "LED3") (pin "A") (pinfunction "A_A") (pintype "passive"))
      (node (ref "R65") (pin "1") (pinfunction "1_1") (pintype "passive"))
    )
    (net (code "99") (name "Net-(LED4-PadA)") (class "Default")
      (node (ref "LED4") (pin "A") (pinfunction "A_A") (pintype "passive"))
      (node (ref "R66") (pin "1") (pinfunction "1_1") (pintype "passive"))
    )
    (net (code "100") (name "Net-(LED5-PadA)") (class "Default")
      (node (ref "LED5") (pin "A") (pinfunction "A_A") (pintype "passive"))
      (node (ref "R67") (pin "1") (pinfunction "1_1") (pintype "passive"))
    )
    (net (code "101") (name "Net-(P2-Pad1)") (class "Default")
      (node (ref "P2") (pin "1") (pinfunction "1_1") (pintype "passive"))
      (node (ref "R44") (pin "2") (pinfunction "2_2") (pintype "passive"))
    )
    (net (code "102") (name "Net-(Q2-PadB)") (class "Default")
      (node (ref "Q2") (pin "B") (pinfunction "B_B") (pintype "passive"))
      (node (ref "R11") (pin "2") (pinfunction "2_2") (pintype "passive"))
    )
    (net (code "103") (name "Net-(Q4-PadB)") (class "Default")
      (node (ref "Q4") (pin "B") (pinfunction "B_B") (pintype "passive"))
      (node (ref "R58") (pin "2") (pinfunction "2_2") (pintype "passive"))
    )
    (net (code "104") (name "Net-(Q5-PadB)") (class "Default")
      (node (ref "Q5") (pin "B") (pinfunction "B_B") (pintype "passive"))
      (node (ref "R60") (pin "2") (pinfunction "2_2") (pintype "passive"))
    )
    (net (code "105") (name "Net-(U1-IN)") (class "Default")
      (node (ref "C2") (pin "+") (pinfunction "+_+") (pintype "passive"))
      (node (ref "R2") (pin "1") (pinfunction "1_1") (pintype "passive"))
      (node (ref "U1") (pin "3") (pinfunction "IN_3") (pintype "input"))
    )
    (net (code "106") (name "PITCH_INPUT") (class "Default")
      (node (ref "D7") (pin "3") (pinfunction "AC_3") (pintype "passive"))
      (node (ref "R64") (pin "2") (pinfunction "2_2") (pintype "passive"))
      (node (ref "U3") (pin "9") (pinfunction "S2_9") (pintype "bidirectional"))
    )
    (net (code "107") (name "PITCH_SOURCE") (class "Default")
      (node (ref "R14") (pin "2") (pinfunction "2_2") (pintype "passive"))
      (node (ref "U3") (pin "6") (pinfunction "D4_6") (pintype "bidirectional"))
      (node (ref "U3") (pin "8") (pinfunction "D2_8") (pintype "bidirectional"))
    )
    (net (code "108") (name "POSITION_ATT") (class "Default")
      (node (ref "R49") (pin "P$2") (pinfunction "S_P$2") (pintype "passive"))
      (node (ref "U4") (pin "15") (pinfunction "Y2_15") (pintype "bidirectional"))
    )
    (net (code "109") (name "POSITION_CV") (class "Default")
      (node (ref "C38") (pin "2") (pinfunction "2_2") (pintype "passive"))
      (node (ref "IC2") (pin "23") (pinfunction "PA7/SPI1_MOSI/ADC7/TIM3_CH2_23") (pintype "bidirectional"))
      (node (ref "IC7") (pin "7") (pinfunction "OUT_7") (pintype "output"))
      (node (ref "R32") (pin "1") (pinfunction "1_1") (pintype "passive"))
    )
    (net (code "110") (name "POSITION_POT") (class "Default")
      (node (ref "R30") (pin "P$2") (pinfunction "S_P$2") (pintype "passive"))
      (node (ref "U4") (pin "12") (pinfunction "Y3_12") (pintype "bidirectional"))
    )
    (net (code "111") (name "RESET") (class "Default")
      (node (ref "IC2") (pin "7") (pinfunction "NRST_7") (pintype "bidirectional"))
      (node (ref "JP1") (pin "10") (pinfunction "10_10") (pintype "passive"))
      (node (ref "R6") (pin "1") (pinfunction "1_1") (pintype "passive"))
      (node (ref "SW3") (pin "B") (pinfunction "S_B") (pintype "passive"))
      (node (ref "SW3") (pin "B'") (pinfunction "S1_B'") (pintype "passive"))
    )
    (net (code "112") (name "RX") (class "Default")
      (node (ref "IC2") (pin "43") (pinfunction "PA10/USART1_RX/TIM1_CH3_43") (pintype "bidirectional"))
      (node (ref "JP2") (pin "4") (pinfunction "4_4") (pintype "passive"))
    )
    (net (code "113") (name "STRUM") (class "Default")
      (node (ref "IC2") (pin "16") (pinfunction "PA2/USART2_TX/ADC2/TIM2_CH3_16") (pintype "bidirectional"))
      (node (ref "Q2") (pin "C") (pinfunction "C_C") (pintype "passive"))
      (node (ref "R8") (pin "1") (pinfunction "1_1") (pintype "passive"))
    )
    (net (code "114") (name "STRUM_INPUT") (class "Default")
      (node (ref "D5") (pin "3") (pinfunction "AC_3") (pintype "passive"))
      (node (ref "R62") (pin "2") (pinfunction "2_2") (pintype "passive"))
      (node (ref "U2") (pin "16") (pinfunction "S1_16") (pintype "bidirectional"))
    )
    (net (code "115") (name "STRUM_NORM") (class "Default")
      (node (ref "R52") (pin "2") (pinfunction "2_2") (pintype "passive"))
      (node (ref "U2") (pin "4") (pinfunction "S3_4") (pintype "bidirectional"))
    )
    (net (code "116") (name "STRUM_SOURCE") (class "Default")
      (node (ref "R11") (pin "1") (pinfunction "1_1") (pintype "passive"))
      (node (ref "U2") (pin "1") (pinfunction "D1_1") (pintype "bidirectional"))
      (node (ref "U2") (pin "3") (pinfunction "D3_3") (pintype "bidirectional"))
    )
    (net (code "117") (name "SW_MODE") (class "Default")
      (node (ref "IC2") (pin "61") (pinfunction "PB8/TIM4_CH3/I2C1_SCL_61") (pintype "bidirectional"))
      (node (ref "SW10") (pin "3") (pinfunction "3_3") (pintype "passive"))
      (node (ref "SW10") (pin "4") (pinfunction "4_4") (pintype "passive"))
    )
    (net (code "118") (name "SW_POLYPHONY") (class "Default")
      (node (ref "IC2") (pin "62") (pinfunction "PB9/SPI2_NSS/I2S2_WS/I2C1_SDA/TIM4_CH4_62") (pintype "bidirectional"))
      (node (ref "SW11") (pin "3") (pinfunction "3_3") (pintype "passive"))
      (node (ref "SW11") (pin "4") (pinfunction "4_4") (pintype "passive"))
    )
    (net (code "119") (name "TX") (class "Default")
      (node (ref "IC2") (pin "42") (pinfunction "PA9/USART1_TX/TIM1_CH2_42") (pintype "bidirectional"))
      (node (ref "JP2") (pin "5") (pinfunction "5_5") (pintype "passive"))
    )
    (net (code "120") (name "VBAT") (class "Default")
      (node (ref "IC2") (pin "1") (pinfunction "VBAT_1") (pintype "power_in"))
    )
    (net (code "121") (name "VCC") (class "Default")
      (node (ref "C3") (pin "+") (pinfunction "+_+") (pintype "passive"))
      (node (ref "C39") (pin "1") (pinfunction "1_1") (pintype "passive"))
      (node (ref "D5") (pin "2") (pinfunction "C_2") (pintype "passive"))
      (node (ref "D6") (pin "2") (pinfunction "C_2") (pintype "passive"))
      (node (ref "D7") (pin "2") (pinfunction "C_2") (pintype "passive"))
      (node (ref "IC8") (pin "8") (pinfunction "V+_8") (pintype "power_in"))
      (node (ref "L1") (pin "1") (pinfunction "1_1") (pintype "passive"))
      (node (ref "U2") (pin "11") (pinfunction "VDD_11") (pintype "bidirectional"))
      (node (ref "U3") (pin "11") (pinfunction "VDD_11") (pintype "bidirectional"))
    )
    (net (code "122") (name "VEE") (class "Default")
      (node (ref "C1") (pin "-") (pinfunction "-_-") (pintype "passive"))
      (node (ref "C45") (pin "2") (pinfunction "2_2") (pintype "passive"))
      (node (ref "D5") (pin "1") (pinfunction "A_1") (pintype "passive"))
      (node (ref "D6") (pin "1") (pinfunction "A_1") (pintype "passive"))
      (node (ref "D7") (pin "1") (pinfunction "A_1") (pintype "passive"))
      (node (ref "IC8") (pin "4") (pinfunction "V-_4") (pintype "power_in"))
      (node (ref "L2") (pin "1") (pinfunction "1_1") (pintype "passive"))
      (node (ref "R12") (pin "1") (pinfunction "1_1") (pintype "passive"))
      (node (ref "U2") (pin "14") (pinfunction "VEE_14") (pintype "bidirectional"))
      (node (ref "U3") (pin "14") (pinfunction "VEE_14") (pintype "bidirectional"))
    )
    (net (code "123") (name "V_OCT_CV") (class "Default")
      (node (ref "C14") (pin "2") (pinfunction "2_2") (pintype "passive"))
      (node (ref "IC2") (pin "15") (pinfunction "PA1/USART2_RTS/UART4_RX/ADC1/TIM2_CH2_15") (pintype "bidirectional"))
      (node (ref "IC5") (pin "7") (pinfunction "OUT_7") (pintype "output"))
      (node (ref "R13") (pin "1") (pinfunction "1_1") (pintype "passive"))
    )
    (net (code "124") (name "unconnected-(IC2-PA11{slash}USART1_CTS{slash}CANRX{slash}USBDM{slash}TIM1_CH4-Pad44)") (class "Default")
      (node (ref "IC2") (pin "44") (pinfunction "PA11/USART1_CTS/CANRX/USBDM/TIM1_CH4_44") (pintype "bidirectional"))
    )
    (net (code "125") (name "unconnected-(IC2-PA12{slash}USART1_RTS{slash}CANTX{slash}USBDP{slash}TIM1_ETR-Pad45)") (class "Default")
      (node (ref "IC2") (pin "45") (pinfunction "PA12/USART1_RTS/CANTX/USBDP/TIM1_ETR_45") (pintype "bidirectional"))
    )
    (net (code "126") (name "unconnected-(IC2-PC9{slash}I2S2_CKIN{slash}I2S3_CKIN-Pad40)") (class "Default")
      (node (ref "IC2") (pin "40") (pinfunction "PC9/I2S2_CKIN/I2S3_CKIN_40") (pintype "bidirectional"))
    )
    (net (code "127") (name "unconnected-(IC2-PC13-TAMPER-RTC-Pad2)") (class "Default")
      (node (ref "IC2") (pin "2") (pinfunction "PC13-TAMPER-RTC_2") (pintype "bidirectional"))
    )
    (net (code "128") (name "unconnected-(IC2-PC14{slash}OSC32_IN-Pad3)") (class "Default")
      (node (ref "IC2") (pin "3") (pinfunction "PC14/OSC32_IN_3") (pintype "bidirectional"))
    )
    (net (code "129") (name "unconnected-(IC2-PC15{slash}OSC_OUT-Pad4)") (class "Default")
      (node (ref "IC2") (pin "4") (pinfunction "PC15/OSC_OUT_4") (pintype "bidirectional"))
    )
    (net (code "130") (name "unconnected-(IC2-PD2{slash}TIM3-ETR-Pad54)") (class "Default")
      (node (ref "IC2") (pin "54") (pinfunction "PD2/TIM3-ETR_54") (pintype "bidirectional"))
    )
    (net (code "131") (name "unconnected-(IC6-CLKOUT-Pad2)") (class "Default")
      (node (ref "IC6") (pin "2") (pinfunction "CLKOUT_2") (pintype "bidirectional"))
    )
    (net (code "132") (name "unconnected-(IC6-LHPOUT-Pad9)") (class "Default")
      (node (ref "IC6") (pin "9") (pinfunction "LHPOUT_9") (pintype "bidirectional"))
    )
    (net (code "133") (name "unconnected-(IC6-MICBIAS-Pad17)") (class "Default")
      (node (ref "IC6") (pin "17") (pinfunction "MICBIAS_17") (pintype "bidirectional"))
    )
    (net (code "134") (name "unconnected-(IC6-MICIN-Pad18)") (class "Default")
      (node (ref "IC6") (pin "18") (pinfunction "MICIN_18") (pintype "bidirectional"))
    )
    (net (code "135") (name "unconnected-(IC6-RHPOUT-Pad10)") (class "Default")
      (node (ref "IC6") (pin "10") (pinfunction "RHPOUT_10") (pintype "bidirectional"))
    )
    (net (code "136") (name "unconnected-(JP1-Pad7)") (class "Default")
      (node (ref "JP1") (pin "7") (pinfunction "7_7") (pintype "passive"))
    )
    (net (code "137") (name "unconnected-(JP2-Pad2)") (class "Default")
      (node (ref "JP2") (pin "2") (pinfunction "2_2") (pintype "passive"))
    )
    (net (code "138") (name "unconnected-(JP2-Pad3)") (class "Default")
      (node (ref "JP2") (pin "3") (pinfunction "3_3") (pintype "passive"))
    )
    (net (code "139") (name "unconnected-(JP2-Pad6)") (class "Default")
      (node (ref "JP2") (pin "6") (pinfunction "6_6") (pintype "passive"))
    )
    (net (code "140") (name "unconnected-(P1-Pad4)") (class "Default")
      (node (ref "P1") (pin "4") (pinfunction "4_4") (pintype "passive"))
    )
    (net (code "141") (name "unconnected-(P1-Pad6)") (class "Default")
      (node (ref "P1") (pin "6") (pinfunction "6_6") (pintype "passive"))
    )
    (net (code "142") (name "unconnected-(P2-Pad3)") (class "Default")
      (node (ref "P2") (pin "3") (pinfunction "3_3") (pintype "passive"))
    )
    (net (code "143") (name "unconnected-(U2-NC1-Pad2)") (class "Default")
      (node (ref "U2") (pin "2") (pinfunction "NC1_2") (pintype "bidirectional"))
    )
    (net (code "144") (name "unconnected-(U2-NC2-Pad7)") (class "Default")
      (node (ref "U2") (pin "7") (pinfunction "NC2_7") (pintype "bidirectional"))
    )
    (net (code "145") (name "unconnected-(U3-NC1-Pad2)") (class "Default")
      (node (ref "U3") (pin "2") (pinfunction "NC1_2") (pintype "bidirectional"))
    )
    (net (code "146") (name "unconnected-(U3-NC2-Pad7)") (class "Default")
      (node (ref "U3") (pin "7") (pinfunction "NC2_7") (pintype "bidirectional"))
    )
  )
)
